# plugwatch.net
KiCad netlist of a schematic drawn in EAGLE
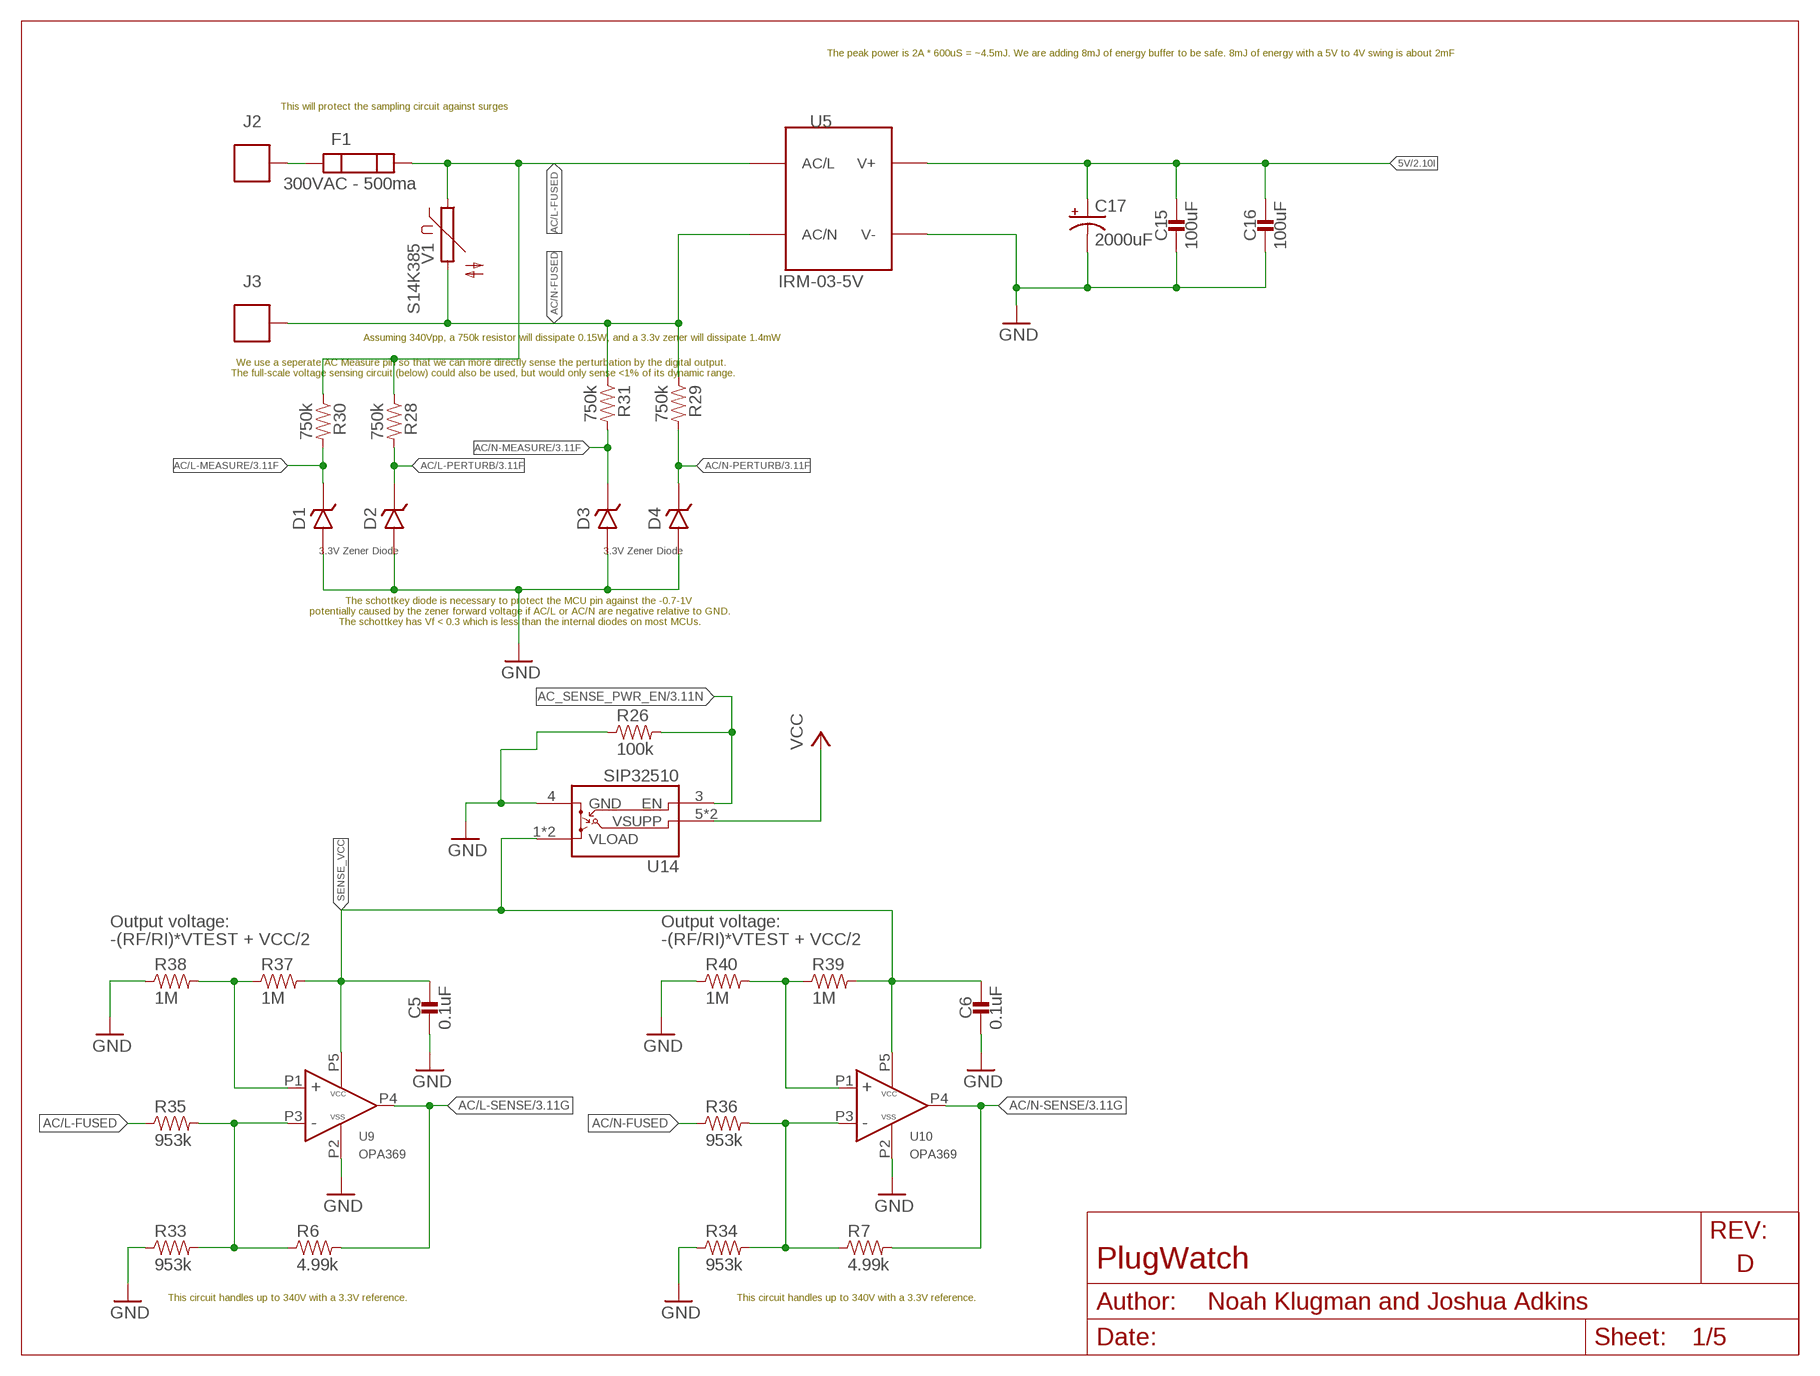
[diagram p0: schematic, sheet 1]
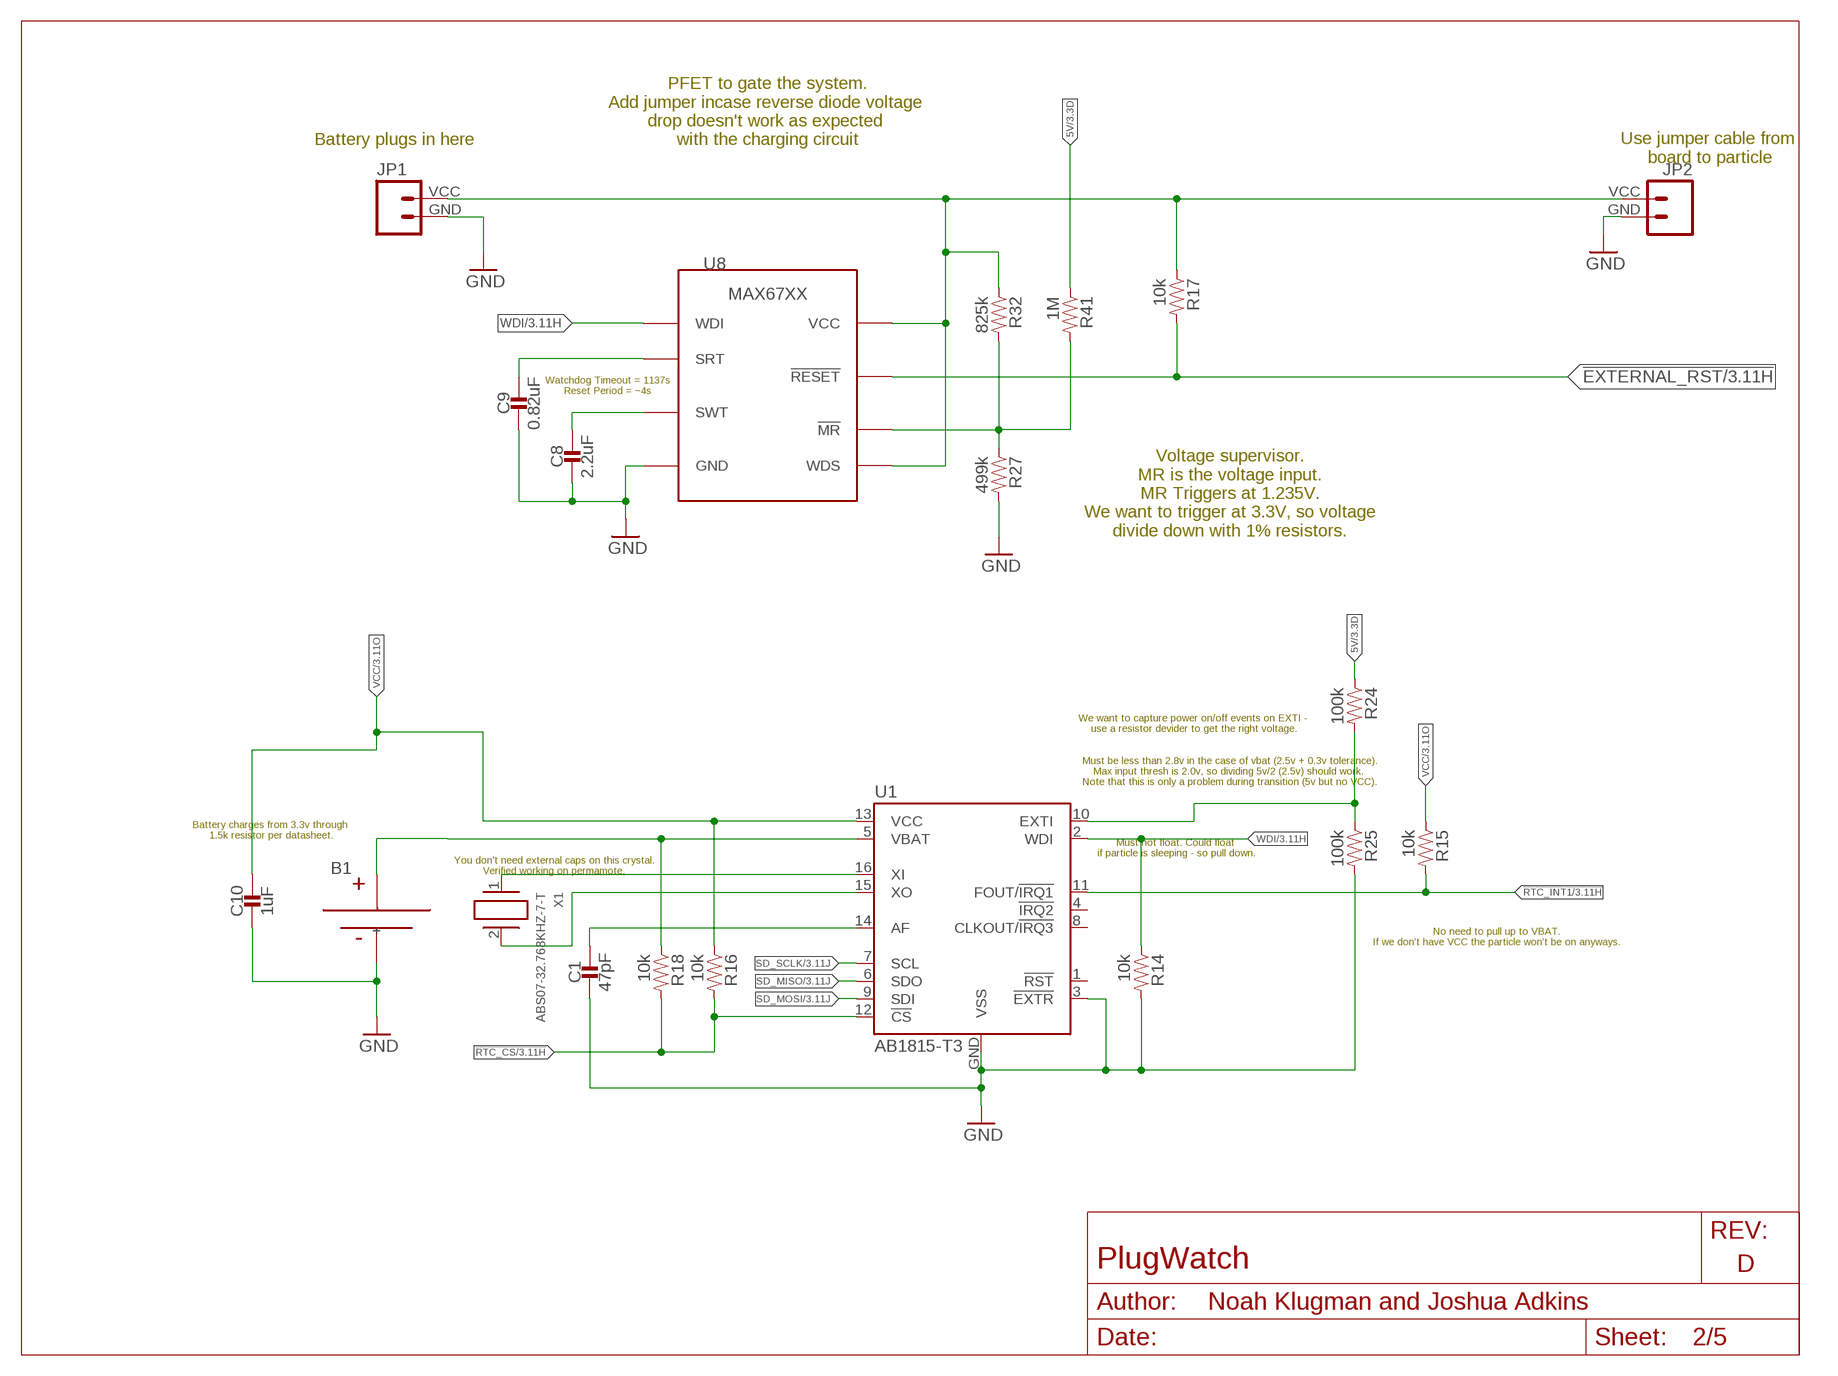
[diagram p1: schematic, sheet 2]
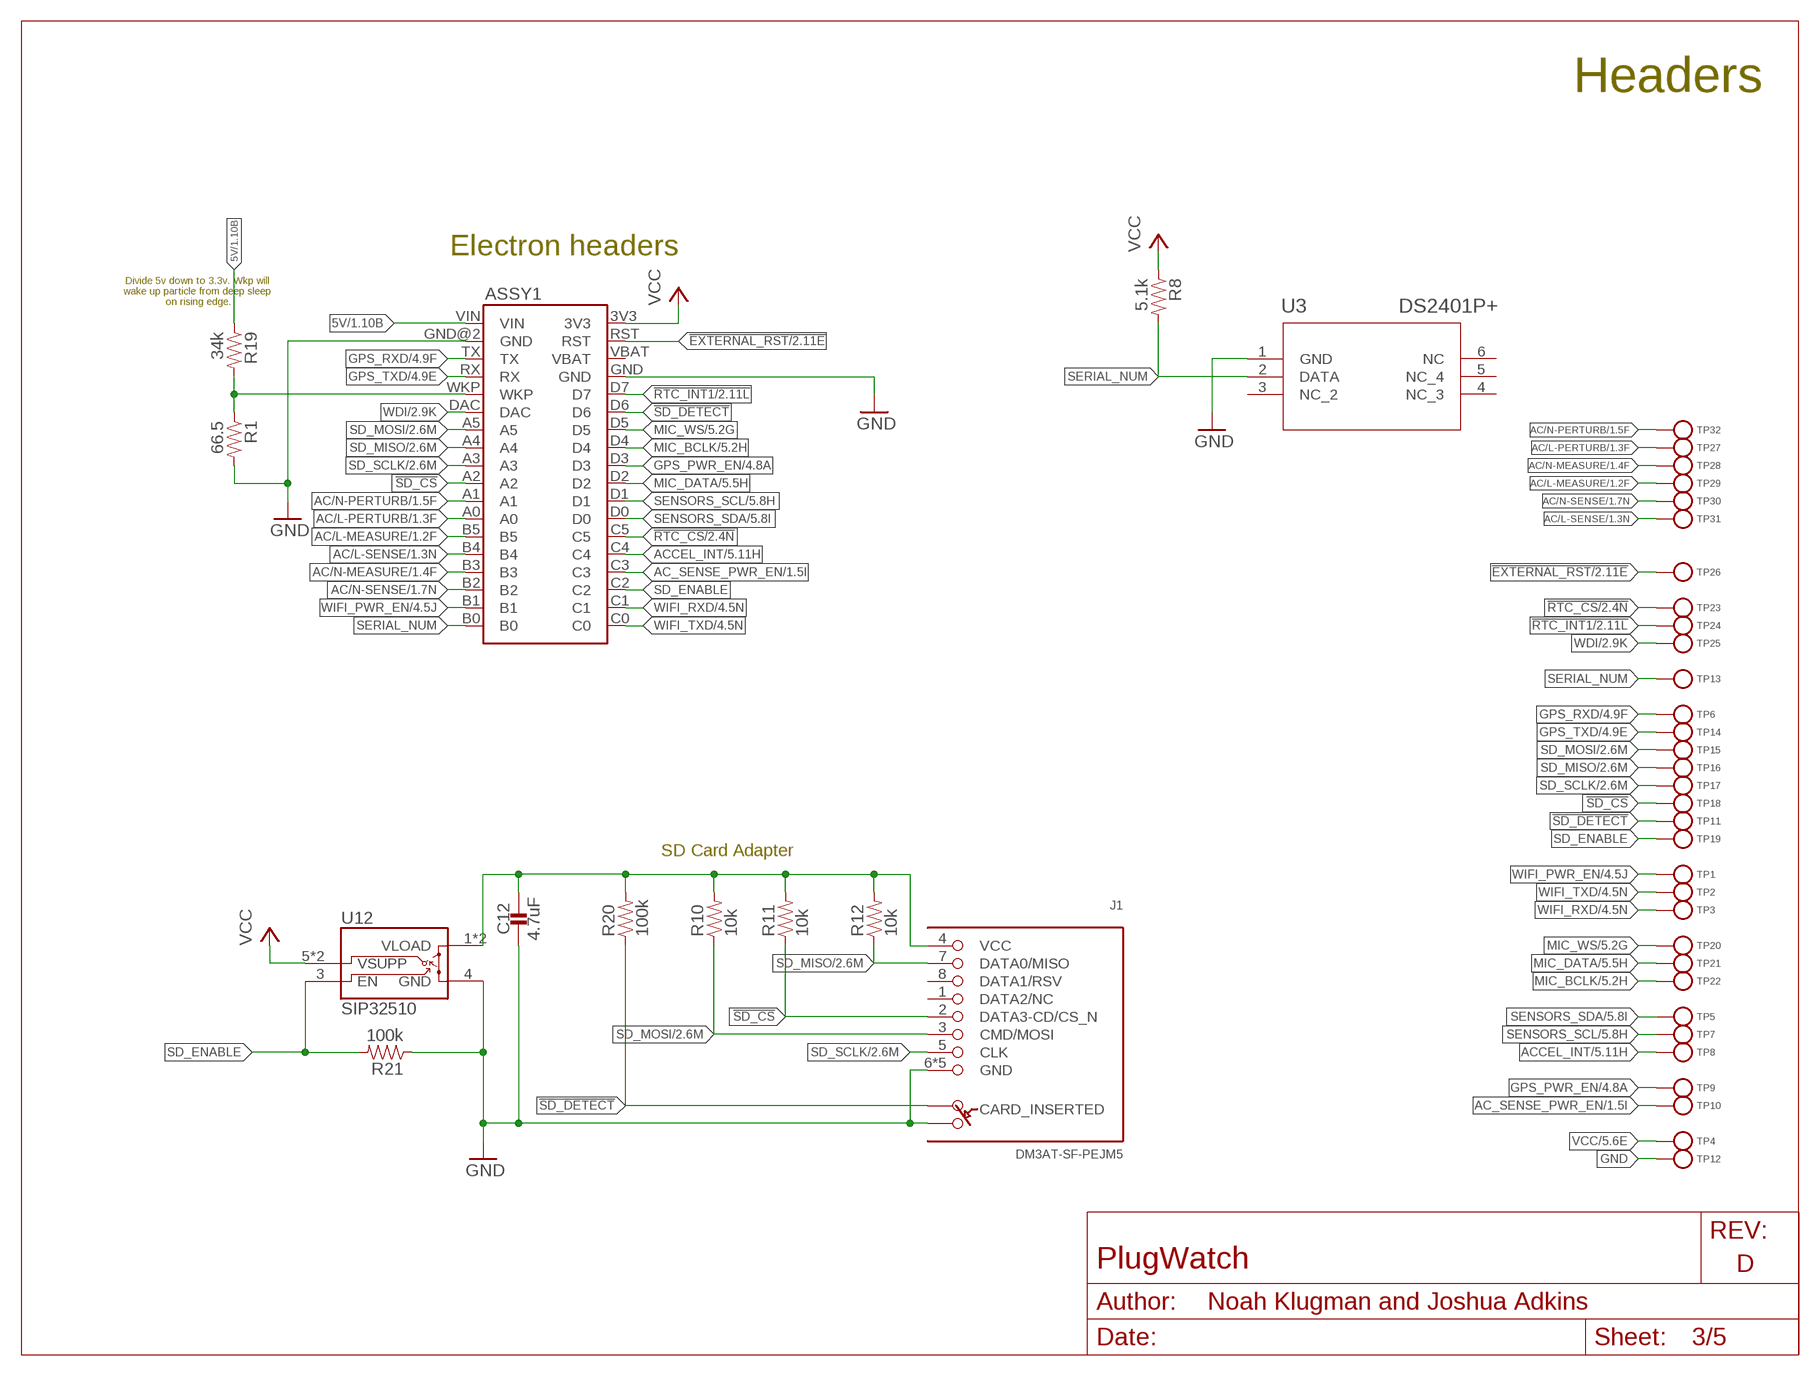
[diagram p2: schematic, sheet 3]
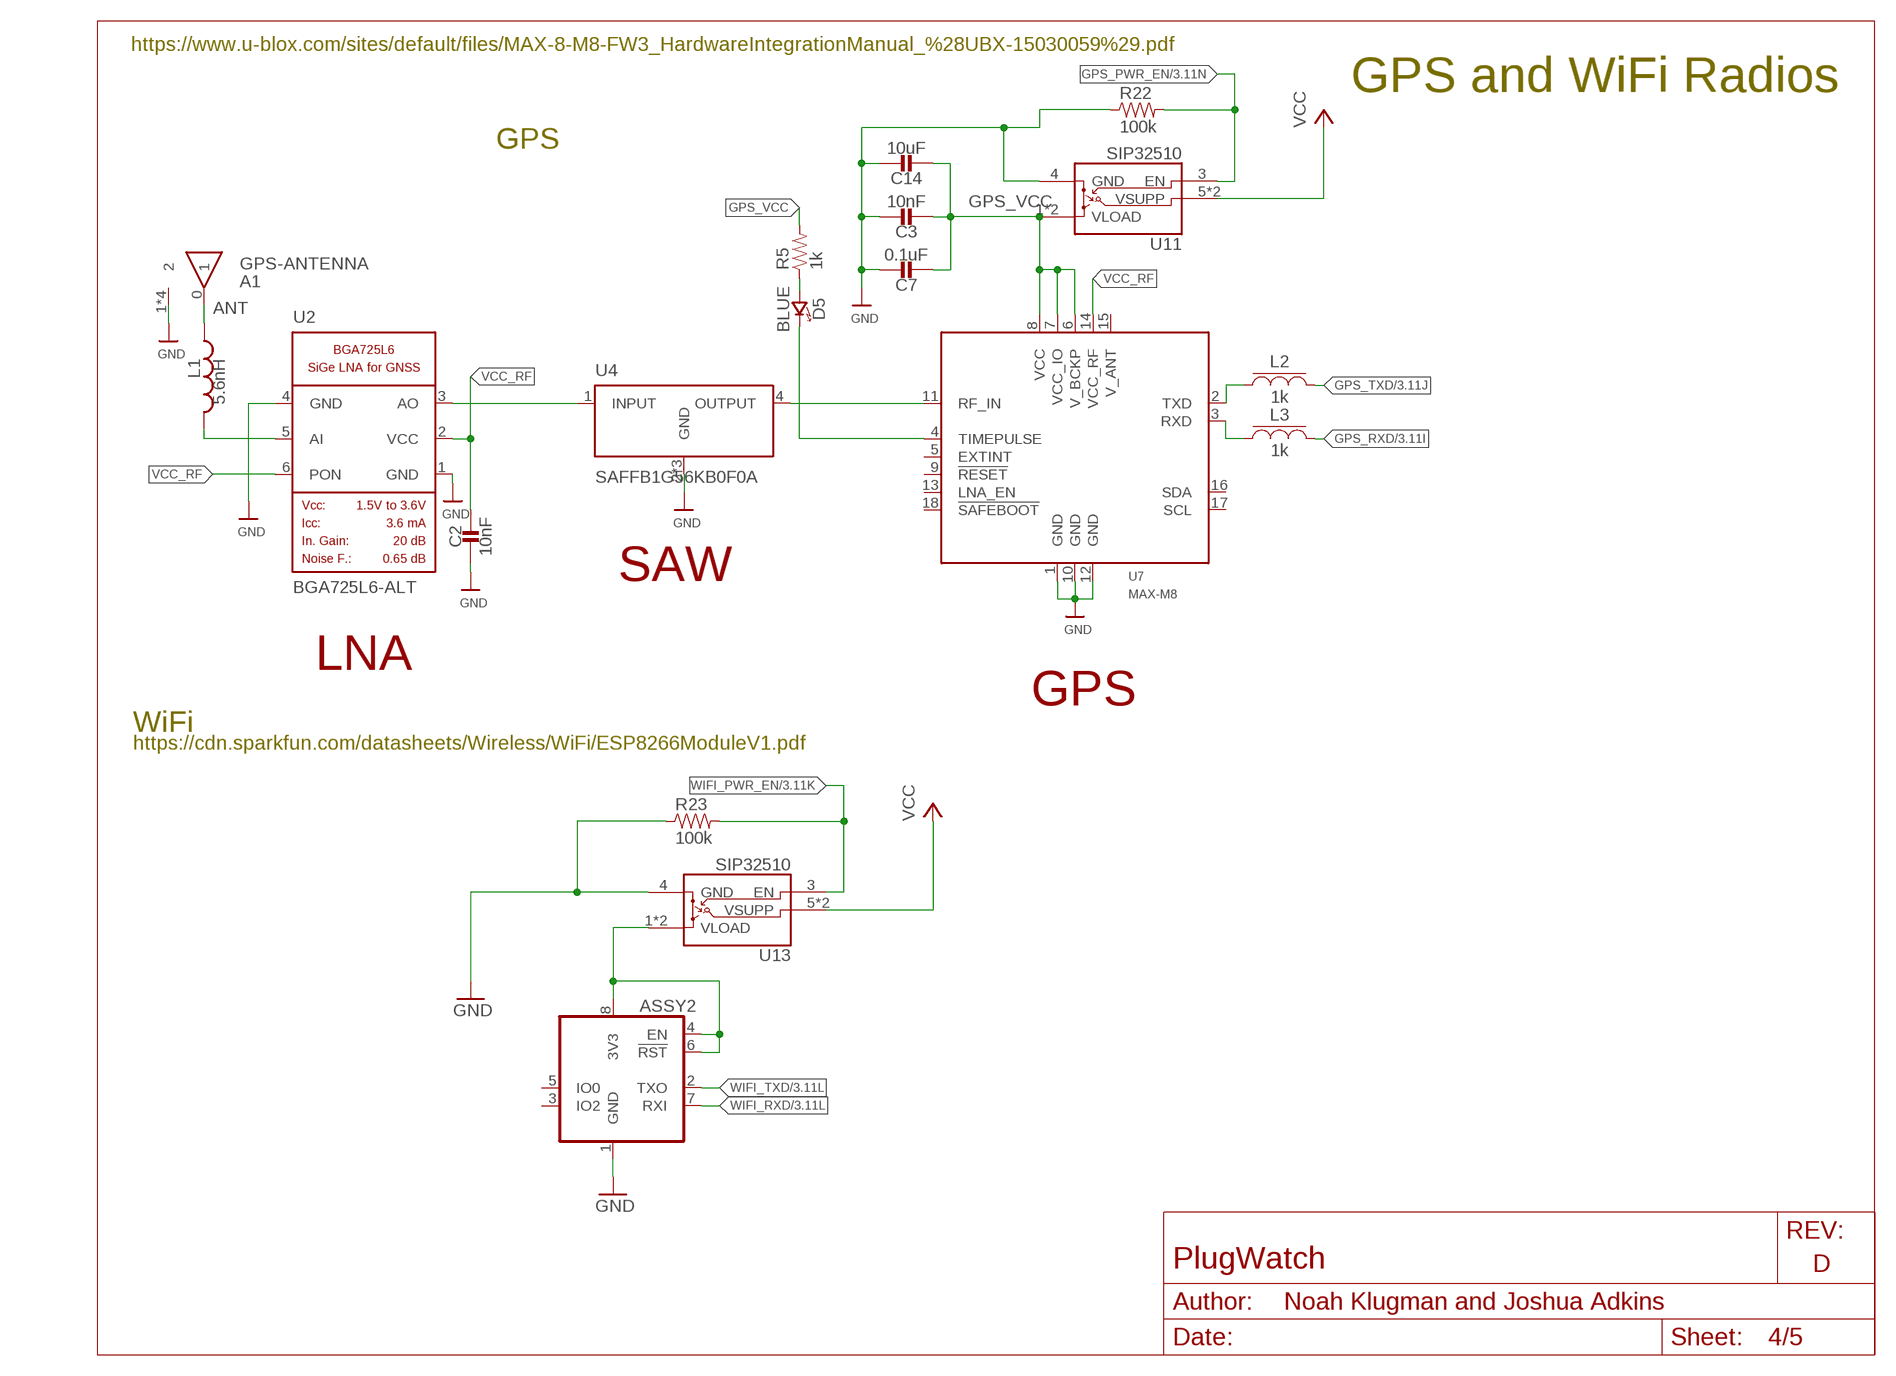
[diagram p3: schematic, sheet 4]
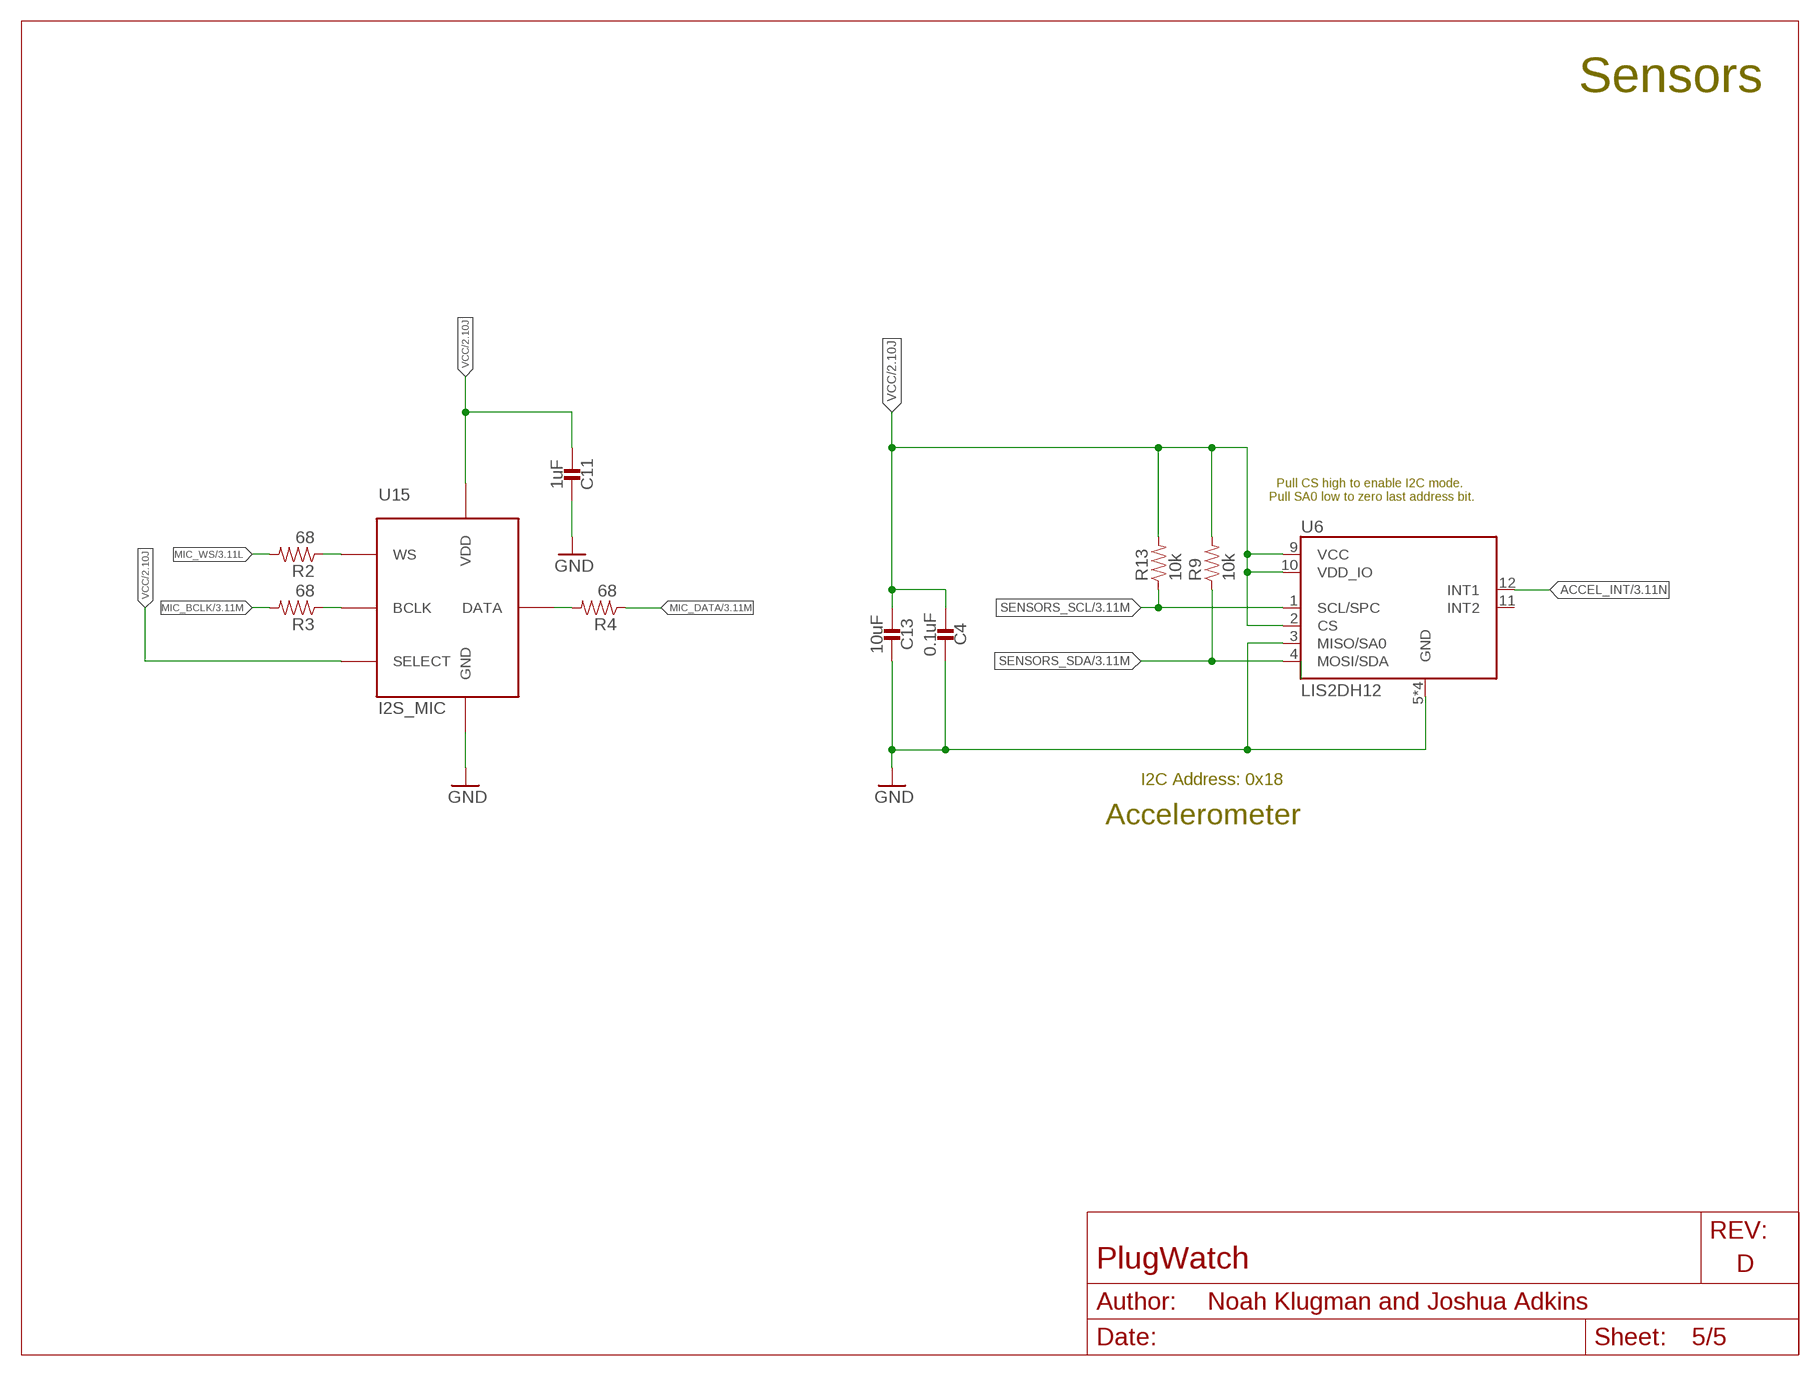
[diagram p4: schematic, sheet 5]

(export (version "E")
  (design (tool "Eeschema 10.0.6"))
  (components
    (comp (ref "A1")
      (value "GPS-ANTENNA")
      (footprint "eagle-import:ANT1818B00BT1516S")
      (description "PATCH ANT GPS/GLO CP SMD")
      (fields (field (name "MANUFACTURER") "Yageo") (field (name "MPN") "ANT1818B00BT1516S"))
      (libsource (lib "eagle-import") (part "GPS-ANTENNA"))
    )
    (comp (ref "ASSY2")
      (value "WRL-13678")
      (footprint "eagle-import:WRL-13678")
      (libsource (lib "eagle-import") (part "WRL-13678"))
    )
    (comp (ref "C2")
      (value "10nF")
      (footprint "eagle-import:0402_CAP")
      (description "CAP CER 10000PF 16V X7R 0402")
      (fields
        (field (name "MANUFACTURER") "Murata Electronics North America")
        (field (name "MPN") "GRM155R71C103KA01D")
      )
      (libsource (lib "eagle-import") (part "CAPACITOR0402_CAP"))
    )
    (comp (ref "C3")
      (value "10nF")
      (footprint "eagle-import:0402_CAP")
      (description "CAP CER 10000PF 16V X7R 0402")
      (fields
        (field (name "MANUFACTURER") "Murata Electronics North America")
        (field (name "MPN") "GRM155R71C103KA01D")
      )
      (libsource (lib "eagle-import") (part "CAPACITOR0402_CAP"))
    )
    (comp (ref "C7")
      (value "0.1uF")
      (footprint "eagle-import:0402_CAP")
      (description "CAP CER 0.1UF 10V X5R 0402")
      (fields (field (name "MANUFACTURER") "Yageo") (field (name "MPN") "CC0402KRX5R6BB104"))
      (libsource (lib "eagle-import") (part "CAPACITOR0402_CAP"))
    )
    (comp (ref "C14")
      (value "10uF")
      (footprint "eagle-import:0402_CAP")
      (description "CAP CER 10UF 6.3V X5R 0402")
      (fields
        (field (name "MANUFACTURER") "Murata Electronics North America")
        (field (name "MPN") "GRJ155R60J106ME11D")
      )
      (libsource (lib "eagle-import") (part "CAPACITOR0402_CAP"))
    )
    (comp (ref "D5")
      (value "BLUE")
      (footprint "eagle-import:LED-0603")
      (description "LED BLUE CLEAR SMD")
      (fields (field (name "MANUFACTURER") "Lite-On Inc.") (field (name "MPN") "LTST-C194TBKT"))
      (libsource (lib "eagle-import") (part "LED0603"))
    )
    (comp (ref "L1")
      (value "5.6nH")
      (footprint "eagle-import:0402_CAP")
      (description "FIXED IND 5.6NH 1.77A 40 MOHM")
      (fields (field (name "MANUFACTURER") "Murata") (field (name "MPN") "LQW15AN5N6B80D"))
      (libsource (lib "eagle-import") (part "INDUCTOR0402"))
    )
    (comp (ref "L2")
      (value "1k")
      (footprint "eagle-import:0402_CAP")
      (description "FERRITE BEAD 1 KOHM 0402 1LN")
      (fields (field (name "MANUFACTURER") "Murata") (field (name "MPN") "BLM15HD102SN1D"))
      (libsource (lib "eagle-import") (part "FERRITE_BEAD0402"))
    )
    (comp (ref "L3")
      (value "1k")
      (footprint "eagle-import:0402_CAP")
      (description "FERRITE BEAD 1 KOHM 0402 1LN")
      (fields (field (name "MANUFACTURER") "Murata") (field (name "MPN") "BLM15HD102SN1D"))
      (libsource (lib "eagle-import") (part "FERRITE_BEAD0402"))
    )
    (comp (ref "R5")
      (value "1k")
      (footprint "eagle-import:0402_RES")
      (description "RES SMD 1K OHM 1% 1/16W 0402")
      (fields (field (name "MANUFACTURER") "Stackpole Electronics") (field (name "MPN") "RMCF0402FT1K00"))
      (libsource (lib "eagle-import") (part "RESISTOR0402_RES"))
    )
    (comp (ref "R22")
      (value "100k")
      (footprint "eagle-import:0402_RES")
      (description "RES SMD 100K OHM 1% 1/16W 0402")
      (fields (field (name "MANUFACTURER") "Vishay Dale") (field (name "MPN") "CRCW0402100KFKED"))
      (libsource (lib "eagle-import") (part "RESISTOR0402_RES"))
    )
    (comp (ref "R23")
      (value "100k")
      (footprint "eagle-import:0402_RES")
      (description "RES SMD 100K OHM 1% 1/16W 0402")
      (fields (field (name "MANUFACTURER") "Vishay Dale") (field (name "MPN") "CRCW0402100KFKED"))
      (libsource (lib "eagle-import") (part "RESISTOR0402_RES"))
    )
    (comp (ref "U2")
      (value "BGA725L6-ALT")
      (footprint "eagle-import:LNA-TSLP-6-2-ALT")
      (description "IC AMP MMIC RF LNA 20DB TSLP-6")
      (fields (field (name "MANUFACTURER") "Infineon") (field (name "MPN") "BGA725L6E6327FTSA1"))
      (libsource (lib "eagle-import") (part "BGA725L6-ALT"))
    )
    (comp (ref "U4")
      (value "SAFFB1G56KB0F0A")
      (footprint "eagle-import:QCS5I")
      (description "FILTER SAW 1.582GHZ 5SMD")
      (fields (field (name "MANUFACTURER") "Taiyo Yuden") (field (name "MPN") "F6QA1G582H2JM-J"))
      (libsource (lib "eagle-import") (part "FILTERS"))
    )
    (comp (ref "U7")
      (value "MAX-M8")
      (footprint "eagle-import:MAX-M8")
      (description "IC RECEIVER GPS/GNSS 18LCC")
      (fields (field (name "MANUFACTURER") "u-blox") (field (name "MPN") "MAX-M8Q-0"))
      (libsource (lib "eagle-import") (part "MAX-M8"))
    )
    (comp (ref "U11")
      (value "SIP32510")
      (footprint "eagle-import:TSOT23-6")
      (fields (field (name "MANUFACTURER") "Vishay") (field (name "MPN") "SIP32510DT-T1-GE3"))
      (libsource (lib "eagle-import") (part "SIP32510"))
    )
    (comp (ref "U13")
      (value "SIP32510")
      (footprint "eagle-import:TSOT23-6")
      (fields (field (name "MANUFACTURER") "Vishay") (field (name "MPN") "SIP32510DT-T1-GE3"))
      (libsource (lib "eagle-import") (part "SIP32510"))
    )
    (comp (ref "B1")
      (value "MS518SE")
      (footprint "eagle-import:MS518SE-FL35E")
      (fields (field (name "MANUFACTURER") "Seiko") (field (name "MPN") "MS518SE-FL35E"))
      (libsource (lib "eagle-import") (part "MS518SE"))
    )
    (comp (ref "C1")
      (value "47pF")
      (footprint "eagle-import:0402_CAP")
      (description "CAP CER 47PF 100V C0G/NP0 0402")
      (fields
        (field (name "MANUFACTURER") "Murata Electronics North America")
        (field (name "MPN") "GRM1555C2A470JA01D")
      )
      (libsource (lib "eagle-import") (part "CAPACITOR0402_CAP"))
    )
    (comp (ref "C8")
      (value "2.2uF")
      (footprint "eagle-import:0402_CAP")
      (fields
        (field (name "MANUFACTURER") "Murata Electronics North America")
        (field (name "MPN") "GRM155C70J225KE11D")
      )
      (libsource (lib "eagle-import") (part "CAPACITOR0402_CAP"))
    )
    (comp (ref "C9")
      (value "0.82uF")
      (footprint "eagle-import:0402_CAP")
      (fields
        (field (name "MANUFACTURER") "Murata Electronics North America")
        (field (name "MPN") "GRM155C80J824KE15D")
      )
      (libsource (lib "eagle-import") (part "CAPACITOR0402_CAP"))
    )
    (comp (ref "C10")
      (value "1uF")
      (footprint "eagle-import:0402_CAP")
      (description "CAP CER 1UF 10V X7S 0402")
      (fields
        (field (name "MANUFACTURER") "Murata Electronics North America")
        (field (name "MPN") "GCM155C71A105KE38D")
      )
      (libsource (lib "eagle-import") (part "CAPACITOR0402_CAP"))
    )
    (comp (ref "JP1")
      (value "M024UCON-15767")
      (footprint "eagle-import:JST-2-SMD-VERT")
      (description "CONN HEADER PH TOP 2POS 2MM SMD")
      (fields
        (field (name "MANUFACTURER") "JST Sales America Inc.")
        (field (name "MPN") "B2B-PH-SM4-TB(LF)(SN)")
      )
      (libsource (lib "eagle-import") (part "M024UCON-15767"))
    )
    (comp (ref "JP2")
      (value "M024UCON-15767")
      (footprint "eagle-import:JST-2-SMD-VERT")
      (description "CONN HEADER PH TOP 2POS 2MM SMD")
      (fields
        (field (name "MANUFACTURER") "JST Sales America Inc.")
        (field (name "MPN") "B2B-PH-SM4-TB(LF)(SN)")
      )
      (libsource (lib "eagle-import") (part "M024UCON-15767"))
    )
    (comp (ref "R14")
      (value "10k")
      (footprint "eagle-import:0402_RES")
      (description "RES SMD 10K OHM 1% 1/16W 0402")
      (fields
        (field (name "MANUFACTURER") "Stackpole Electronics Inc. ")
        (field (name "MPN") "RMCF0402FT10K0 ")
      )
      (libsource (lib "eagle-import") (part "RESISTOR0402_RES"))
    )
    (comp (ref "R15")
      (value "10k")
      (footprint "eagle-import:0402_RES")
      (description "RES SMD 10K OHM 1% 1/16W 0402")
      (fields
        (field (name "MANUFACTURER") "Stackpole Electronics Inc. ")
        (field (name "MPN") "RMCF0402FT10K0 ")
      )
      (libsource (lib "eagle-import") (part "RESISTOR0402_RES"))
    )
    (comp (ref "R16")
      (value "10k")
      (footprint "eagle-import:0402_RES")
      (description "RES SMD 10K OHM 1% 1/16W 0402")
      (fields
        (field (name "MANUFACTURER") "Stackpole Electronics Inc. ")
        (field (name "MPN") "RMCF0402FT10K0 ")
      )
      (libsource (lib "eagle-import") (part "RESISTOR0402_RES"))
    )
    (comp (ref "R17")
      (value "10k")
      (footprint "eagle-import:0402_RES")
      (description "RES SMD 10K OHM 1% 1/16W 0402")
      (fields
        (field (name "MANUFACTURER") "Stackpole Electronics Inc. ")
        (field (name "MPN") "RMCF0402FT10K0 ")
      )
      (libsource (lib "eagle-import") (part "RESISTOR0402_RES"))
    )
    (comp (ref "R18")
      (value "10k")
      (footprint "eagle-import:0402_RES")
      (description "RES SMD 10K OHM 1% 1/16W 0402")
      (fields
        (field (name "MANUFACTURER") "Stackpole Electronics Inc. ")
        (field (name "MPN") "RMCF0402FT10K0 ")
      )
      (libsource (lib "eagle-import") (part "RESISTOR0402_RES"))
    )
    (comp (ref "R24")
      (value "100k")
      (footprint "eagle-import:0402_RES")
      (description "RES SMD 100K OHM 1% 1/16W 0402")
      (fields (field (name "MANUFACTURER") "Vishay Dale") (field (name "MPN") "CRCW0402100KFKED"))
      (libsource (lib "eagle-import") (part "RESISTOR0402_RES"))
    )
    (comp (ref "R25")
      (value "100k")
      (footprint "eagle-import:0402_RES")
      (description "RES SMD 100K OHM 1% 1/16W 0402")
      (fields (field (name "MANUFACTURER") "Vishay Dale") (field (name "MPN") "CRCW0402100KFKED"))
      (libsource (lib "eagle-import") (part "RESISTOR0402_RES"))
    )
    (comp (ref "R27")
      (value "499k")
      (footprint "eagle-import:0402_RES")
      (description "RES SMD 499K OHM 1% 1/10W 0402")
      (fields
        (field (name "MANUFACTURER") "Panasonic Electronic Components")
        (field (name "MPN") "ERJ-2RKF4993X")
      )
      (libsource (lib "eagle-import") (part "RESISTOR0402_RES"))
    )
    (comp (ref "R32")
      (value "825k")
      (footprint "eagle-import:0402_RES")
      (description "RES SMD 825K OHM 1% 1/10W 0402")
      (fields
        (field (name "MANUFACTURER") "Panasonic Electronic Components")
        (field (name "MPN") "ERJ-2RKF8253X")
      )
      (libsource (lib "eagle-import") (part "RESISTOR0402_RES"))
    )
    (comp (ref "R41")
      (value "1M")
      (footprint "eagle-import:0402_RES")
      (description "RES 1M OHM 1% 1/16W 0402")
      (fields
        (field (name "MANUFACTURER") "Stackpole Electronics Inc.")
        (field (name "MPN") "RMCF0402FT1M00")
      )
      (libsource (lib "eagle-import") (part "RESISTOR0402_RES"))
    )
    (comp (ref "U1")
      (value "AB1815-T3")
      (footprint "eagle-import:QFN-16-3MM")
      (fields (field (name "MANUFACTURER") "Abracon"))
      (libsource (lib "eagle-import") (part "AB1815-T3"))
    )
    (comp (ref "U8")
      (value "MAX67XXMAX6749MAX67XX")
      (footprint "eagle-import:SOT-23-8")
      (fields (field (name "MANUFACTURER") "Maxim Integrated") (field (name "MPN") "MAX6749KA+T"))
      (libsource (lib "eagle-import") (part "MAX67XXMAX67XXMAX6749"))
    )
    (comp (ref "X1")
      (value "ABS07-32.768KHZ-7-T")
      (footprint "eagle-import:2-SMD")
      (fields (field (name "MANUFACTURER") "ABRACON") (field (name "MPN") "ABS07-32.768KHZ-7-T "))
      (libsource (lib "eagle-import") (part "ABS07-32.768KHZ-7-T"))
    )
    (comp (ref "C4")
      (value "0.1uF")
      (footprint "eagle-import:0402_CAP")
      (description "CAP CER 0.1UF 10V X5R 0402")
      (fields (field (name "MANUFACTURER") "Yageo") (field (name "MPN") "CC0402KRX5R6BB104"))
      (libsource (lib "eagle-import") (part "CAPACITOR0402_CAP"))
    )
    (comp (ref "C11")
      (value "1uF")
      (footprint "eagle-import:0402_CAP")
      (description "CAP CER 1UF 10V X7S 0402")
      (fields
        (field (name "MANUFACTURER") "Murata Electronics North America")
        (field (name "MPN") "GCM155C71A105KE38D")
      )
      (libsource (lib "eagle-import") (part "CAPACITOR0402_CAP"))
    )
    (comp (ref "C13")
      (value "10uF")
      (footprint "eagle-import:0402_CAP")
      (description "CAP CER 10UF 6.3V X5R 0402")
      (fields
        (field (name "MANUFACTURER") "Murata Electronics North America")
        (field (name "MPN") "GRJ155R60J106ME11D")
      )
      (libsource (lib "eagle-import") (part "CAPACITOR0402_CAP"))
    )
    (comp (ref "R2")
      (value "68")
      (footprint "eagle-import:0402_RES")
      (description "RES SMD 68 OHM 1% 1/16W 0402")
      (fields (field (name "MANUFACTURER") "Yageo") (field (name "MPN") "RC0402FR-0768RL"))
      (libsource (lib "eagle-import") (part "RESISTOR0402_RES"))
    )
    (comp (ref "R3")
      (value "68")
      (footprint "eagle-import:0402_RES")
      (description "RES SMD 68 OHM 1% 1/16W 0402")
      (fields (field (name "MANUFACTURER") "Yageo") (field (name "MPN") "RC0402FR-0768RL"))
      (libsource (lib "eagle-import") (part "RESISTOR0402_RES"))
    )
    (comp (ref "R4")
      (value "68")
      (footprint "eagle-import:0402_RES")
      (description "RES SMD 68 OHM 1% 1/16W 0402")
      (fields (field (name "MANUFACTURER") "Yageo") (field (name "MPN") "RC0402FR-0768RL"))
      (libsource (lib "eagle-import") (part "RESISTOR0402_RES"))
    )
    (comp (ref "R9")
      (value "10k")
      (footprint "eagle-import:0402_RES")
      (description "RES SMD 10K OHM 1% 1/16W 0402")
      (fields
        (field (name "MANUFACTURER") "Stackpole Electronics Inc. ")
        (field (name "MPN") "RMCF0402FT10K0 ")
      )
      (libsource (lib "eagle-import") (part "RESISTOR0402_RES"))
    )
    (comp (ref "R13")
      (value "10k")
      (footprint "eagle-import:0402_RES")
      (description "RES SMD 10K OHM 1% 1/16W 0402")
      (fields
        (field (name "MANUFACTURER") "Stackpole Electronics Inc. ")
        (field (name "MPN") "RMCF0402FT10K0 ")
      )
      (libsource (lib "eagle-import") (part "RESISTOR0402_RES"))
    )
    (comp (ref "U6")
      (value "LIS2DH12")
      (footprint "eagle-import:LGA-12")
      (fields
        (field (name "MANUFACTURER") "STMicroelectronics")
        (field (name "MPN") "LIS2DW12TR")
        (field (name "DIGIKEY") "497-14851-1-ND")
        (field (name "MOUSER") "511-LIS2DH12TR")
        (field (name "MPN_1") "LIS2DH12TR")
      )
      (libsource (lib "eagle-import") (part "LIS2DW12"))
    )
    (comp (ref "U15")
      (value "SPH0645LM4H-B")
      (footprint "eagle-import:SPH0465")
      (fields (field (name "MANUFACTURER") "Knowles"))
      (libsource (lib "eagle-import") (part "SPH0645LM4H-B"))
    )
    (comp (ref "C5")
      (value "0.1uF")
      (footprint "eagle-import:0402_CAP")
      (description "CAP CER 0.1UF 10V X5R 0402")
      (fields (field (name "MANUFACTURER") "Yageo") (field (name "MPN") "CC0402KRX5R6BB104"))
      (libsource (lib "eagle-import") (part "CAPACITOR0402_CAP"))
    )
    (comp (ref "C6")
      (value "0.1uF")
      (footprint "eagle-import:0402_CAP")
      (description "CAP CER 0.1UF 10V X5R 0402")
      (fields (field (name "MANUFACTURER") "Yageo") (field (name "MPN") "CC0402KRX5R6BB104"))
      (libsource (lib "eagle-import") (part "CAPACITOR0402_CAP"))
    )
    (comp (ref "C15")
      (value "100uF")
      (footprint "eagle-import:1210_CAP")
      (description "CAP CER 100UF 6.3V X7S 1210")
      (fields
        (field (name "MANUFACTURER") "Murata Electronics North America")
        (field (name "MPN") "GRM32EC70J107ME15L")
      )
      (libsource (lib "eagle-import") (part "CAPACITOR1210_CAP"))
    )
    (comp (ref "C16")
      (value "100uF")
      (footprint "eagle-import:1210_CAP")
      (description "CAP CER 100UF 6.3V X7S 1210")
      (fields
        (field (name "MANUFACTURER") "Murata Electronics North America")
        (field (name "MPN") "GRM32EC70J107ME15L")
      )
      (libsource (lib "eagle-import") (part "CAPACITOR1210_CAP"))
    )
    (comp (ref "C17")
      (value "2000uF")
      (footprint "eagle-import:E5-13")
      (description "CAP ALUM 2000UF 20% 6.3V T/H")
      (fields
        (field (name "MANUFACTURER") "Panasonic Electronic Components")
        (field (name "MPN") "EEU-FS0J202B")
      )
      (libsource (lib "eagle-import") (part "CPOL-USE5-13"))
    )
    (comp (ref "D1")
      (value "DIODE_ZENERSOT323")
      (footprint "eagle-import:SOD323")
      (description "DIODE ZENER 3.3V 200MW SOD323F")
      (fields (field (name "MANUFACTURER") "ON Semiconductor ") (field (name "MPN") "MM3Z3V3B "))
      (libsource (lib "eagle-import") (part "DIODE_ZENERSOT323"))
    )
    (comp (ref "D2")
      (value "DIODE_ZENERSOT323")
      (footprint "eagle-import:SOD323")
      (description "DIODE ZENER 3.3V 200MW SOD323F")
      (fields (field (name "MANUFACTURER") "ON Semiconductor ") (field (name "MPN") "MM3Z3V3B "))
      (libsource (lib "eagle-import") (part "DIODE_ZENERSOT323"))
    )
    (comp (ref "D3")
      (value "DIODE_ZENERSOT323")
      (footprint "eagle-import:SOD323")
      (description "DIODE ZENER 3.3V 200MW SOD323F")
      (fields (field (name "MANUFACTURER") "ON Semiconductor ") (field (name "MPN") "MM3Z3V3B "))
      (libsource (lib "eagle-import") (part "DIODE_ZENERSOT323"))
    )
    (comp (ref "D4")
      (value "DIODE_ZENERSOT323")
      (footprint "eagle-import:SOD323")
      (description "DIODE ZENER 3.3V 200MW SOD323F")
      (fields (field (name "MANUFACTURER") "ON Semiconductor ") (field (name "MPN") "MM3Z3V3B "))
      (libsource (lib "eagle-import") (part "DIODE_ZENERSOT323"))
    )
    (comp (ref "F1")
      (value "300VAC - 500ma")
      (footprint "eagle-import:MIRCRO_FUSE_5MM")
      (description "FUSE BRD MNT 500MA 350VAC 100VDC")
      (fields (field (name "MANUFACTURER") "Bel Fuse Inc") (field (name "MPN") "0697H0500-01"))
      (libsource (lib "eagle-import") (part "MICRO_FUSE500MA_350VAC"))
    )
    (comp (ref "J2")
      (value "SCREW_TERMNIAL_1")
      (footprint "eagle-import:360272-TERMINAL-BLOCK")
      (fields (field (name "MANUFACTURER") "METZ CONNECT USA Inc.") (field (name "MPN") "360272"))
      (libsource (lib "eagle-import") (part "SCREW_TERMNIAL_1"))
    )
    (comp (ref "J3")
      (value "SCREW_TERMNIAL_1")
      (footprint "eagle-import:360272-TERMINAL-BLOCK")
      (fields (field (name "MANUFACTURER") "METZ CONNECT USA Inc.") (field (name "MPN") "360272"))
      (libsource (lib "eagle-import") (part "SCREW_TERMNIAL_1"))
    )
    (comp (ref "R6")
      (value "4.99k")
      (footprint "eagle-import:0402_RES")
      (description "RES SMD 4.99K OHM 1% 1/10W 0402")
      (fields
        (field (name "MANUFACTURER") "Panasonic Electronic Components")
        (field (name "MPN") "ERJ-2RKF4991X")
      )
      (libsource (lib "eagle-import") (part "RESISTOR0402_RES"))
    )
    (comp (ref "R7")
      (value "4.99k")
      (footprint "eagle-import:0402_RES")
      (description "RES SMD 4.99K OHM 1% 1/10W 0402")
      (fields
        (field (name "MANUFACTURER") "Panasonic Electronic Components")
        (field (name "MPN") "ERJ-2RKF4991X")
      )
      (libsource (lib "eagle-import") (part "RESISTOR0402_RES"))
    )
    (comp (ref "R26")
      (value "100k")
      (footprint "eagle-import:0402_RES")
      (description "RES SMD 100K OHM 1% 1/16W 0402")
      (fields (field (name "MANUFACTURER") "Vishay Dale") (field (name "MPN") "CRCW0402100KFKED"))
      (libsource (lib "eagle-import") (part "RESISTOR0402_RES"))
    )
    (comp (ref "R28")
      (value "750k")
      (footprint "eagle-import:1206_RES_HIGH_CLEARANCE")
      (description "RES SMD 750K OHM 1% 1/4W 1206")
      (fields (field (name "MANUFACTURER") "Yageo") (field (name "MPN") "RC1206FR-07750KL"))
      (libsource (lib "eagle-import") (part "RESISTOR1206_RES_HIGH_CLEARANCE"))
    )
    (comp (ref "R29")
      (value "750k")
      (footprint "eagle-import:1206_RES_HIGH_CLEARANCE")
      (description "RES SMD 750K OHM 1% 1/4W 1206")
      (fields (field (name "MANUFACTURER") "Yageo") (field (name "MPN") "RC1206FR-07750KL"))
      (libsource (lib "eagle-import") (part "RESISTOR1206_RES_HIGH_CLEARANCE"))
    )
    (comp (ref "R30")
      (value "750k")
      (footprint "eagle-import:1206_RES_HIGH_CLEARANCE")
      (description "RES SMD 750K OHM 1% 1/4W 1206")
      (fields (field (name "MANUFACTURER") "Yageo") (field (name "MPN") "RC1206FR-07750KL"))
      (libsource (lib "eagle-import") (part "RESISTOR1206_RES_HIGH_CLEARANCE"))
    )
    (comp (ref "R31")
      (value "750k")
      (footprint "eagle-import:1206_RES_HIGH_CLEARANCE")
      (description "RES SMD 750K OHM 1% 1/4W 1206")
      (fields (field (name "MANUFACTURER") "Yageo") (field (name "MPN") "RC1206FR-07750KL"))
      (libsource (lib "eagle-import") (part "RESISTOR1206_RES_HIGH_CLEARANCE"))
    )
    (comp (ref "R33")
      (value "953k")
      (footprint "eagle-import:0402_RES")
      (description "RES SMD 953K OHM 1% 1/16W 0402")
      (fields (field (name "MANUFACTURER") "Yageo") (field (name "MPN") "RC0402FR-07953KL"))
      (libsource (lib "eagle-import") (part "RESISTOR0402_RES"))
    )
    (comp (ref "R34")
      (value "953k")
      (footprint "eagle-import:0402_RES")
      (description "RES SMD 953K OHM 1% 1/16W 0402")
      (fields (field (name "MANUFACTURER") "Yageo") (field (name "MPN") "RC0402FR-07953KL"))
      (libsource (lib "eagle-import") (part "RESISTOR0402_RES"))
    )
    (comp (ref "R35")
      (value "953k")
      (footprint "eagle-import:1206_RES_HIGH_CLEARANCE")
      (fields
        (field (name "MANUFACTURER") "Panasonic Electronic Components")
        (field (name "MPN") "ERA-8AEB9533V")
      )
      (libsource (lib "eagle-import") (part "RESISTOR1206_RES_HIGH_CLEARANCE"))
    )
    (comp (ref "R36")
      (value "953k")
      (footprint "eagle-import:1206_RES_HIGH_CLEARANCE")
      (fields
        (field (name "MANUFACTURER") "Panasonic Electronic Components")
        (field (name "MPN") "ERA-8AEB9533V")
      )
      (libsource (lib "eagle-import") (part "RESISTOR1206_RES_HIGH_CLEARANCE"))
    )
    (comp (ref "R37")
      (value "1M")
      (footprint "eagle-import:0402_RES")
      (description "RES 1M OHM 1% 1/16W 0402")
      (fields
        (field (name "MANUFACTURER") "Stackpole Electronics Inc.")
        (field (name "MPN") "RMCF0402FT1M00")
      )
      (libsource (lib "eagle-import") (part "RESISTOR0402_RES"))
    )
    (comp (ref "R38")
      (value "1M")
      (footprint "eagle-import:0402_RES")
      (description "RES 1M OHM 1% 1/16W 0402")
      (fields
        (field (name "MANUFACTURER") "Stackpole Electronics Inc.")
        (field (name "MPN") "RMCF0402FT1M00")
      )
      (libsource (lib "eagle-import") (part "RESISTOR0402_RES"))
    )
    (comp (ref "R39")
      (value "1M")
      (footprint "eagle-import:0402_RES")
      (description "RES 1M OHM 1% 1/16W 0402")
      (fields
        (field (name "MANUFACTURER") "Stackpole Electronics Inc.")
        (field (name "MPN") "RMCF0402FT1M00")
      )
      (libsource (lib "eagle-import") (part "RESISTOR0402_RES"))
    )
    (comp (ref "R40")
      (value "1M")
      (footprint "eagle-import:0402_RES")
      (description "RES 1M OHM 1% 1/16W 0402")
      (fields
        (field (name "MANUFACTURER") "Stackpole Electronics Inc.")
        (field (name "MPN") "RMCF0402FT1M00")
      )
      (libsource (lib "eagle-import") (part "RESISTOR0402_RES"))
    )
    (comp (ref "U5")
      (value "IRM-03-5V")
      (footprint "eagle-import:IRM-03")
      (fields (field (name "MANUFACTURER") "Mean Well USA") (field (name "MPN") "IRM-03-5"))
      (libsource (lib "eagle-import") (part "IRM-03-5V"))
    )
    (comp (ref "U9")
      (value "OPA369")
      (footprint "eagle-import:SC70-5")
      (fields
        (field (name "MANUFACTURER") "Texas Instruments")
        (field (name "MPN") "OPA369AIDCKR")
        (field (name "DIGIKEY") "296-25252-1-ND")
      )
      (libsource (lib "eagle-import") (part "OPA369"))
    )
    (comp (ref "U10")
      (value "OPA369")
      (footprint "eagle-import:SC70-5")
      (fields
        (field (name "MANUFACTURER") "Texas Instruments")
        (field (name "MPN") "OPA369AIDCKR")
        (field (name "DIGIKEY") "296-25252-1-ND")
      )
      (libsource (lib "eagle-import") (part "OPA369"))
    )
    (comp (ref "U14")
      (value "SIP32510")
      (footprint "eagle-import:TSOT23-6")
      (fields (field (name "MANUFACTURER") "Vishay") (field (name "MPN") "SIP32510DT-T1-GE3"))
      (libsource (lib "eagle-import") (part "SIP32510"))
    )
    (comp (ref "V1")
      (value "S14K385")
      (footprint "eagle-import:S14K385")
      (description "VARISTOR 620V 5KA DISC 14MM")
      (fields (field (name "MANUFACTURER") "EPCOS (TDK)") (field (name "MPN") "B72214S2381K101"))
      (libsource (lib "eagle-import") (part "S14K385"))
    )
    (comp (ref "ASSY1")
      (value "ELECTRON")
      (footprint "eagle-import:ELECTRON_SINGLE-ROW")
      (description "18 Position header")
      (fields (field (name "MANUFACTURER") "Sullins") (field (name "MPN") "PPPC181LFBN-RC"))
      (libsource (lib "eagle-import") (part "ELECTRON"))
    )
    (comp (ref "C12")
      (value "4.7uF")
      (footprint "eagle-import:0402_CAP")
      (description "CAP CER 4.7UF 6.3V X5R 0402")
      (fields (field (name "MANUFACTURER") "TDK") (field (name "MPN") "C1005X5R0J475K050BC"))
      (libsource (lib "eagle-import") (part "CAPACITOR0402_CAP"))
    )
    (comp (ref "J1")
      (value "DM3AT-SF-PEJM5")
      (footprint "eagle-import:DM3AT-SF-PEJM5")
      (fields (field (name "MANUFACTURER") "Hirose Electric Co Ltd"))
      (libsource (lib "eagle-import") (part "DM3AT-SF-PEJM5"))
    )
    (comp (ref "R1")
      (value "66.5")
      (footprint "eagle-import:0402_RES")
      (description "RES SMD 66.5 OHM 1% 1/16W 0402")
      (fields (field (name "MANUFACTURER") "Yageo") (field (name "MPN") "RC0402FR-0766R5L"))
      (libsource (lib "eagle-import") (part "RESISTOR0402_RES"))
    )
    (comp (ref "R8")
      (value "5.1k")
      (footprint "eagle-import:0402_RES")
      (description "RES SMD 5.1K OHM 1% 1/10W 0402")
      (fields
        (field (name "MANUFACTURER") "Panasonic Electronic Components")
        (field (name "MPN") "ERJ-2RKF5101X")
      )
      (libsource (lib "eagle-import") (part "RESISTOR0402_RES"))
    )
    (comp (ref "R10")
      (value "10k")
      (footprint "eagle-import:0402_RES")
      (description "RES SMD 10K OHM 1% 1/16W 0402")
      (fields
        (field (name "MANUFACTURER") "Stackpole Electronics Inc. ")
        (field (name "MPN") "RMCF0402FT10K0 ")
      )
      (libsource (lib "eagle-import") (part "RESISTOR0402_RES"))
    )
    (comp (ref "R11")
      (value "10k")
      (footprint "eagle-import:0402_RES")
      (description "RES SMD 10K OHM 1% 1/16W 0402")
      (fields
        (field (name "MANUFACTURER") "Stackpole Electronics Inc. ")
        (field (name "MPN") "RMCF0402FT10K0 ")
      )
      (libsource (lib "eagle-import") (part "RESISTOR0402_RES"))
    )
    (comp (ref "R12")
      (value "10k")
      (footprint "eagle-import:0402_RES")
      (description "RES SMD 10K OHM 1% 1/16W 0402")
      (fields
        (field (name "MANUFACTURER") "Stackpole Electronics Inc. ")
        (field (name "MPN") "RMCF0402FT10K0 ")
      )
      (libsource (lib "eagle-import") (part "RESISTOR0402_RES"))
    )
    (comp (ref "R19")
      (value "34k")
      (footprint "eagle-import:0402_RES")
      (description "RES SMD 34K OHM 1% 1/10W 0402")
      (fields
        (field (name "MANUFACTURER") "Panasonic Electronic Components")
        (field (name "MPN") "ERJ-2RKF3402X")
      )
      (libsource (lib "eagle-import") (part "RESISTOR0402_RES"))
    )
    (comp (ref "R20")
      (value "100k")
      (footprint "eagle-import:0402_RES")
      (description "RES SMD 100K OHM 1% 1/16W 0402")
      (fields (field (name "MANUFACTURER") "Vishay Dale") (field (name "MPN") "CRCW0402100KFKED"))
      (libsource (lib "eagle-import") (part "RESISTOR0402_RES"))
    )
    (comp (ref "R21")
      (value "100k")
      (footprint "eagle-import:0402_RES")
      (description "RES SMD 100K OHM 1% 1/16W 0402")
      (fields (field (name "MANUFACTURER") "Vishay Dale") (field (name "MPN") "CRCW0402100KFKED"))
      (libsource (lib "eagle-import") (part "RESISTOR0402_RES"))
    )
    (comp (ref "TP1")
      (value "TEST_POINT_0.040IN")
      (footprint "eagle-import:TESTPOINT_0.040IN")
      (libsource (lib "eagle-import") (part "TEST_POINT_0.040IN"))
    )
    (comp (ref "TP2")
      (value "TEST_POINT_0.040IN")
      (footprint "eagle-import:TESTPOINT_0.040IN")
      (libsource (lib "eagle-import") (part "TEST_POINT_0.040IN"))
    )
    (comp (ref "TP3")
      (value "TEST_POINT_0.040IN")
      (footprint "eagle-import:TESTPOINT_0.040IN")
      (libsource (lib "eagle-import") (part "TEST_POINT_0.040IN"))
    )
    (comp (ref "TP4")
      (value "TEST_POINT_0.040IN")
      (footprint "eagle-import:TESTPOINT_0.040IN")
      (libsource (lib "eagle-import") (part "TEST_POINT_0.040IN"))
    )
    (comp (ref "TP5")
      (value "TEST_POINT_0.040IN")
      (footprint "eagle-import:TESTPOINT_0.040IN")
      (libsource (lib "eagle-import") (part "TEST_POINT_0.040IN"))
    )
    (comp (ref "TP6")
      (value "TEST_POINT_0.040IN")
      (footprint "eagle-import:TESTPOINT_0.040IN")
      (libsource (lib "eagle-import") (part "TEST_POINT_0.040IN"))
    )
    (comp (ref "TP7")
      (value "TEST_POINT_0.040IN")
      (footprint "eagle-import:TESTPOINT_0.040IN")
      (libsource (lib "eagle-import") (part "TEST_POINT_0.040IN"))
    )
    (comp (ref "TP8")
      (value "TEST_POINT_0.040IN")
      (footprint "eagle-import:TESTPOINT_0.040IN")
      (libsource (lib "eagle-import") (part "TEST_POINT_0.040IN"))
    )
    (comp (ref "TP9")
      (value "TEST_POINT_0.040IN")
      (footprint "eagle-import:TESTPOINT_0.040IN")
      (libsource (lib "eagle-import") (part "TEST_POINT_0.040IN"))
    )
    (comp (ref "TP10")
      (value "TEST_POINT_0.040IN")
      (footprint "eagle-import:TESTPOINT_0.040IN")
      (libsource (lib "eagle-import") (part "TEST_POINT_0.040IN"))
    )
    (comp (ref "TP11")
      (value "TEST_POINT_0.040IN")
      (footprint "eagle-import:TESTPOINT_0.040IN")
      (libsource (lib "eagle-import") (part "TEST_POINT_0.040IN"))
    )
    (comp (ref "TP12")
      (value "TEST_POINT_0.040IN")
      (footprint "eagle-import:TESTPOINT_0.040IN")
      (libsource (lib "eagle-import") (part "TEST_POINT_0.040IN"))
    )
    (comp (ref "TP13")
      (value "TEST_POINT_0.040IN")
      (footprint "eagle-import:TESTPOINT_0.040IN")
      (libsource (lib "eagle-import") (part "TEST_POINT_0.040IN"))
    )
    (comp (ref "TP14")
      (value "TEST_POINT_0.040IN")
      (footprint "eagle-import:TESTPOINT_0.040IN")
      (libsource (lib "eagle-import") (part "TEST_POINT_0.040IN"))
    )
    (comp (ref "TP15")
      (value "TEST_POINT_0.040IN")
      (footprint "eagle-import:TESTPOINT_0.040IN")
      (libsource (lib "eagle-import") (part "TEST_POINT_0.040IN"))
    )
    (comp (ref "TP16")
      (value "TEST_POINT_0.040IN")
      (footprint "eagle-import:TESTPOINT_0.040IN")
      (libsource (lib "eagle-import") (part "TEST_POINT_0.040IN"))
    )
    (comp (ref "TP17")
      (value "TEST_POINT_0.040IN")
      (footprint "eagle-import:TESTPOINT_0.040IN")
      (libsource (lib "eagle-import") (part "TEST_POINT_0.040IN"))
    )
    (comp (ref "TP18")
      (value "TEST_POINT_0.040IN")
      (footprint "eagle-import:TESTPOINT_0.040IN")
      (libsource (lib "eagle-import") (part "TEST_POINT_0.040IN"))
    )
    (comp (ref "TP19")
      (value "TEST_POINT_0.040IN")
      (footprint "eagle-import:TESTPOINT_0.040IN")
      (libsource (lib "eagle-import") (part "TEST_POINT_0.040IN"))
    )
    (comp (ref "TP20")
      (value "TEST_POINT_0.040IN")
      (footprint "eagle-import:TESTPOINT_0.040IN")
      (libsource (lib "eagle-import") (part "TEST_POINT_0.040IN"))
    )
    (comp (ref "TP21")
      (value "TEST_POINT_0.040IN")
      (footprint "eagle-import:TESTPOINT_0.040IN")
      (libsource (lib "eagle-import") (part "TEST_POINT_0.040IN"))
    )
    (comp (ref "TP22")
      (value "TEST_POINT_0.040IN")
      (footprint "eagle-import:TESTPOINT_0.040IN")
      (libsource (lib "eagle-import") (part "TEST_POINT_0.040IN"))
    )
    (comp (ref "TP23")
      (value "TEST_POINT_0.040IN")
      (footprint "eagle-import:TESTPOINT_0.040IN")
      (libsource (lib "eagle-import") (part "TEST_POINT_0.040IN"))
    )
    (comp (ref "TP24")
      (value "TEST_POINT_0.040IN")
      (footprint "eagle-import:TESTPOINT_0.040IN")
      (libsource (lib "eagle-import") (part "TEST_POINT_0.040IN"))
    )
    (comp (ref "TP25")
      (value "TEST_POINT_0.040IN")
      (footprint "eagle-import:TESTPOINT_0.040IN")
      (libsource (lib "eagle-import") (part "TEST_POINT_0.040IN"))
    )
    (comp (ref "TP26")
      (value "TEST_POINT_0.040IN")
      (footprint "eagle-import:TESTPOINT_0.040IN")
      (libsource (lib "eagle-import") (part "TEST_POINT_0.040IN"))
    )
    (comp (ref "TP27")
      (value "TEST_POINT_0.040IN")
      (footprint "eagle-import:TESTPOINT_0.040IN")
      (libsource (lib "eagle-import") (part "TEST_POINT_0.040IN"))
    )
    (comp (ref "TP28")
      (value "TEST_POINT_0.040IN")
      (footprint "eagle-import:TESTPOINT_0.040IN")
      (libsource (lib "eagle-import") (part "TEST_POINT_0.040IN"))
    )
    (comp (ref "TP29")
      (value "TEST_POINT_0.040IN")
      (footprint "eagle-import:TESTPOINT_0.040IN")
      (libsource (lib "eagle-import") (part "TEST_POINT_0.040IN"))
    )
    (comp (ref "TP30")
      (value "TEST_POINT_0.040IN")
      (footprint "eagle-import:TESTPOINT_0.040IN")
      (libsource (lib "eagle-import") (part "TEST_POINT_0.040IN"))
    )
    (comp (ref "TP31")
      (value "TEST_POINT_0.040IN")
      (footprint "eagle-import:TESTPOINT_0.040IN")
      (libsource (lib "eagle-import") (part "TEST_POINT_0.040IN"))
    )
    (comp (ref "TP32")
      (value "TEST_POINT_0.040IN")
      (footprint "eagle-import:TESTPOINT_0.040IN")
      (libsource (lib "eagle-import") (part "TEST_POINT_0.040IN"))
    )
    (comp (ref "U3")
      (value "DS2401P+")
      (footprint "eagle-import:21-0382")
      (fields (field (name "MANUFACTURER") "Maxim Integrated") (field (name "SPICEPREFIX") "X"))
      (libsource (lib "eagle-import") (part "DS2401P+"))
    )
    (comp (ref "U12")
      (value "SIP32510")
      (footprint "eagle-import:TSOT23-6")
      (fields (field (name "MANUFACTURER") "Vishay") (field (name "MPN") "SIP32510DT-T1-GE3"))
      (libsource (lib "eagle-import") (part "SIP32510"))
    )
  )
  (nets
    (net (code "1") (name "5V") (class "Default")
      (node (ref "ASSY1") (pin "VIN") (pinfunction "VIN_VIN") (pintype "power_in"))
      (node (ref "C15") (pin "1") (pinfunction "1_1") (pintype "bidirectional"))
      (node (ref "C16") (pin "1") (pinfunction "1_1") (pintype "bidirectional"))
      (node (ref "C17") (pin "+") (pinfunction "+_+") (pintype "passive"))
      (node (ref "R19") (pin "1") (pinfunction "1_1") (pintype "passive"))
      (node (ref "R24") (pin "1") (pinfunction "1_1") (pintype "passive"))
      (node (ref "R41") (pin "1") (pinfunction "1_1") (pintype "passive"))
      (node (ref "U5") (pin "V+") (pinfunction "V+_V+") (pintype "bidirectional"))
    )
    (net (code "2") (name "ACCEL_INT") (class "Default")
      (node (ref "ASSY1") (pin "C4") (pinfunction "C4_C4") (pintype "bidirectional"))
      (node (ref "TP8") (pin "TESTPOINT") (pinfunction "TESTPOINT_TESTPOINT") (pintype "bidirectional"))
      (node (ref "U6") (pin "12") (pinfunction "INT1_12") (pintype "bidirectional"))
    )
    (net (code "3") (name "AC_SENSE_PWR_EN") (class "Default")
      (node (ref "ASSY1") (pin "C3") (pinfunction "C3_C3") (pintype "bidirectional"))
      (node (ref "R26") (pin "2") (pinfunction "2_2") (pintype "passive"))
      (node (ref "TP10") (pin "TESTPOINT") (pinfunction "TESTPOINT_TESTPOINT") (pintype "bidirectional"))
      (node (ref "U14") (pin "3") (pinfunction "EN_3") (pintype "bidirectional"))
    )
    (net (code "4") (name "AC{slash}L-FUSED") (class "Default")
      (node (ref "F1") (pin "P$2") (pinfunction "P$2_P$2") (pintype "bidirectional"))
      (node (ref "R28") (pin "1") (pinfunction "1_1") (pintype "passive"))
      (node (ref "R30") (pin "1") (pinfunction "1_1") (pintype "passive"))
      (node (ref "R35") (pin "1") (pinfunction "1_1") (pintype "passive"))
      (node (ref "U5") (pin "AC/L") (pinfunction "AC/L_AC/L") (pintype "bidirectional"))
      (node (ref "V1") (pin "1") (pinfunction "1_1") (pintype "passive"))
    )
    (net (code "5") (name "AC{slash}L-MEASURE") (class "Default")
      (node (ref "ASSY1") (pin "B5") (pinfunction "B5_B5") (pintype "bidirectional"))
      (node (ref "D1") (pin "P$1") (pinfunction "CATHODE_P$1") (pintype "bidirectional"))
      (node (ref "R30") (pin "2") (pinfunction "2_2") (pintype "passive"))
      (node (ref "TP29") (pin "TESTPOINT") (pinfunction "TESTPOINT_TESTPOINT") (pintype "bidirectional"))
    )
    (net (code "6") (name "AC{slash}L-PERTURB") (class "Default")
      (node (ref "ASSY1") (pin "A0") (pinfunction "A0_A0") (pintype "bidirectional"))
      (node (ref "D2") (pin "P$1") (pinfunction "CATHODE_P$1") (pintype "bidirectional"))
      (node (ref "R28") (pin "2") (pinfunction "2_2") (pintype "passive"))
      (node (ref "TP27") (pin "TESTPOINT") (pinfunction "TESTPOINT_TESTPOINT") (pintype "bidirectional"))
    )
    (net (code "7") (name "AC{slash}L-SENSE") (class "Default")
      (node (ref "ASSY1") (pin "B4") (pinfunction "B4_B4") (pintype "bidirectional"))
      (node (ref "R6") (pin "2") (pinfunction "2_2") (pintype "passive"))
      (node (ref "TP31") (pin "TESTPOINT") (pinfunction "TESTPOINT_TESTPOINT") (pintype "bidirectional"))
      (node (ref "U9") (pin "P4") (pinfunction "OUT_P4") (pintype "bidirectional"))
    )
    (net (code "8") (name "AC{slash}N-FUSED") (class "Default")
      (node (ref "J3") (pin "P$1") (pinfunction "P$1_P$1") (pintype "bidirectional"))
      (node (ref "J3") (pin "P$2") (pinfunction "P$1_P$2") (pintype "bidirectional"))
      (node (ref "R29") (pin "1") (pinfunction "1_1") (pintype "passive"))
      (node (ref "R31") (pin "1") (pinfunction "1_1") (pintype "passive"))
      (node (ref "R36") (pin "1") (pinfunction "1_1") (pintype "passive"))
      (node (ref "U5") (pin "AC/N") (pinfunction "AC/N_AC/N") (pintype "bidirectional"))
      (node (ref "V1") (pin "2") (pinfunction "2_2") (pintype "passive"))
    )
    (net (code "9") (name "AC{slash}N-MEASURE") (class "Default")
      (node (ref "ASSY1") (pin "B3") (pinfunction "B3_B3") (pintype "bidirectional"))
      (node (ref "D3") (pin "P$1") (pinfunction "CATHODE_P$1") (pintype "bidirectional"))
      (node (ref "R31") (pin "2") (pinfunction "2_2") (pintype "passive"))
      (node (ref "TP28") (pin "TESTPOINT") (pinfunction "TESTPOINT_TESTPOINT") (pintype "bidirectional"))
    )
    (net (code "10") (name "AC{slash}N-PERTURB") (class "Default")
      (node (ref "ASSY1") (pin "A1") (pinfunction "A1_A1") (pintype "bidirectional"))
      (node (ref "D4") (pin "P$1") (pinfunction "CATHODE_P$1") (pintype "bidirectional"))
      (node (ref "R29") (pin "2") (pinfunction "2_2") (pintype "passive"))
      (node (ref "TP32") (pin "TESTPOINT") (pinfunction "TESTPOINT_TESTPOINT") (pintype "bidirectional"))
    )
    (net (code "11") (name "AC{slash}N-SENSE") (class "Default")
      (node (ref "ASSY1") (pin "B2") (pinfunction "B2_B2") (pintype "bidirectional"))
      (node (ref "R7") (pin "2") (pinfunction "2_2") (pintype "passive"))
      (node (ref "TP30") (pin "TESTPOINT") (pinfunction "TESTPOINT_TESTPOINT") (pintype "bidirectional"))
      (node (ref "U10") (pin "P4") (pinfunction "OUT_P4") (pintype "bidirectional"))
    )
    (net (code "12") (name "ANT") (class "Default")
      (node (ref "A1") (pin "0") (pinfunction "1_0") (pintype "output"))
      (node (ref "L1") (pin "2") (pinfunction "2_2") (pintype "bidirectional"))
    )
    (net (code "13") (name "GND") (class "Default")
      (node (ref "A1") (pin "1") (pinfunction "2_1") (pintype "power_in"))
      (node (ref "A1") (pin "2") (pinfunction "2_2") (pintype "power_in"))
      (node (ref "A1") (pin "3") (pinfunction "2_3") (pintype "power_in"))
      (node (ref "A1") (pin "4") (pinfunction "2_4") (pintype "power_in"))
      (node (ref "ASSY1") (pin "GND") (pinfunction "GND_GND") (pintype "power_in"))
      (node (ref "ASSY1") (pin "GND@2") (pinfunction "GND_GND@2") (pintype "power_in"))
      (node (ref "ASSY2") (pin "1") (pinfunction "GND_1") (pintype "power_in"))
      (node (ref "B1") (pin "-") (pinfunction "-_-") (pintype "bidirectional"))
      (node (ref "C1") (pin "2") (pinfunction "2_2") (pintype "bidirectional"))
      (node (ref "C10") (pin "2") (pinfunction "2_2") (pintype "bidirectional"))
      (node (ref "C11") (pin "2") (pinfunction "2_2") (pintype "bidirectional"))
      (node (ref "C12") (pin "2") (pinfunction "2_2") (pintype "bidirectional"))
      (node (ref "C13") (pin "2") (pinfunction "2_2") (pintype "bidirectional"))
      (node (ref "C14") (pin "1") (pinfunction "1_1") (pintype "bidirectional"))
      (node (ref "C15") (pin "2") (pinfunction "2_2") (pintype "bidirectional"))
      (node (ref "C16") (pin "2") (pinfunction "2_2") (pintype "bidirectional"))
      (node (ref "C17") (pin "-") (pinfunction "-_-") (pintype "passive"))
      (node (ref "C2") (pin "1") (pinfunction "1_1") (pintype "bidirectional"))
      (node (ref "C3") (pin "1") (pinfunction "1_1") (pintype "bidirectional"))
      (node (ref "C4") (pin "2") (pinfunction "2_2") (pintype "bidirectional"))
      (node (ref "C5") (pin "2") (pinfunction "2_2") (pintype "bidirectional"))
      (node (ref "C6") (pin "2") (pinfunction "2_2") (pintype "bidirectional"))
      (node (ref "C7") (pin "1") (pinfunction "1_1") (pintype "bidirectional"))
      (node (ref "C8") (pin "2") (pinfunction "2_2") (pintype "bidirectional"))
      (node (ref "C9") (pin "2") (pinfunction "2_2") (pintype "bidirectional"))
      (node (ref "D1") (pin "P$2") (pinfunction "ANODE_P$2") (pintype "bidirectional"))
      (node (ref "D2") (pin "P$2") (pinfunction "ANODE_P$2") (pintype "bidirectional"))
      (node (ref "D3") (pin "P$2") (pinfunction "ANODE_P$2") (pintype "bidirectional"))
      (node (ref "D4") (pin "P$2") (pinfunction "ANODE_P$2") (pintype "bidirectional"))
      (node (ref "J1") (pin "6") (pinfunction "GND_6") (pintype "bidirectional"))
      (node (ref "J1") (pin "B") (pinfunction "B_B") (pintype "bidirectional"))
      (node (ref "J1") (pin "MOUNT0") (pinfunction "GND_MOUNT0") (pintype "bidirectional"))
      (node (ref "J1") (pin "MOUNT1") (pinfunction "GND_MOUNT1") (pintype "bidirectional"))
      (node (ref "J1") (pin "MOUNT2") (pinfunction "GND_MOUNT2") (pintype "bidirectional"))
      (node (ref "J1") (pin "MOUNT3") (pinfunction "GND_MOUNT3") (pintype "bidirectional"))
      (node (ref "JP1") (pin "GND") (pinfunction "1_GND") (pintype "passive"))
      (node (ref "JP2") (pin "GND") (pinfunction "1_GND") (pintype "passive"))
      (node (ref "R1") (pin "2") (pinfunction "2_2") (pintype "passive"))
      (node (ref "R14") (pin "2") (pinfunction "2_2") (pintype "passive"))
      (node (ref "R21") (pin "1") (pinfunction "1_1") (pintype "passive"))
      (node (ref "R22") (pin "1") (pinfunction "1_1") (pintype "passive"))
      (node (ref "R23") (pin "1") (pinfunction "1_1") (pintype "passive"))
      (node (ref "R25") (pin "2") (pinfunction "2_2") (pintype "passive"))
      (node (ref "R26") (pin "1") (pinfunction "1_1") (pintype "passive"))
      (node (ref "R27") (pin "2") (pinfunction "2_2") (pintype "passive"))
      (node (ref "R33") (pin "1") (pinfunction "1_1") (pintype "passive"))
      (node (ref "R34") (pin "1") (pinfunction "1_1") (pintype "passive"))
      (node (ref "R38") (pin "1") (pinfunction "1_1") (pintype "passive"))
      (node (ref "R40") (pin "1") (pinfunction "1_1") (pintype "passive"))
      (node (ref "TP12") (pin "TESTPOINT") (pinfunction "TESTPOINT_TESTPOINT") (pintype "bidirectional"))
      (node (ref "U1") (pin "3") (pinfunction "~{EXTR}_3") (pintype "bidirectional"))
      (node (ref "U1") (pin "GND") (pinfunction "VSS_GND") (pintype "bidirectional"))
      (node (ref "U10") (pin "P2") (pinfunction "VSS_P2") (pintype "bidirectional"))
      (node (ref "U11") (pin "4") (pinfunction "GND_4") (pintype "bidirectional"))
      (node (ref "U12") (pin "4") (pinfunction "GND_4") (pintype "bidirectional"))
      (node (ref "U13") (pin "4") (pinfunction "GND_4") (pintype "bidirectional"))
      (node (ref "U14") (pin "4") (pinfunction "GND_4") (pintype "bidirectional"))
      (node (ref "U15") (pin "3") (pinfunction "GND_3") (pintype "bidirectional"))
      (node (ref "U2") (pin "1") (pinfunction "GND_1") (pintype "power_in"))
      (node (ref "U2") (pin "4") (pinfunction "GND_4") (pintype "power_in"))
      (node (ref "U3") (pin "1") (pinfunction "GND_1") (pintype "power_in"))
      (node (ref "U4") (pin "2") (pinfunction "GND_2") (pintype "power_in"))
      (node (ref "U4") (pin "3") (pinfunction "GND_3") (pintype "power_in"))
      (node (ref "U4") (pin "5") (pinfunction "GND_5") (pintype "power_in"))
      (node (ref "U5") (pin "V-") (pinfunction "V-_V-") (pintype "bidirectional"))
      (node (ref "U6") (pin "3") (pinfunction "MISO/SA0_3") (pintype "bidirectional"))
      (node (ref "U6") (pin "5") (pinfunction "GND_5") (pintype "bidirectional"))
      (node (ref "U6") (pin "6") (pinfunction "GND_6") (pintype "bidirectional"))
      (node (ref "U6") (pin "7") (pinfunction "GND_7") (pintype "bidirectional"))
      (node (ref "U6") (pin "8") (pinfunction "GND_8") (pintype "bidirectional"))
      (node (ref "U7") (pin "1") (pinfunction "GND_1") (pintype "bidirectional"))
      (node (ref "U7") (pin "10") (pinfunction "GND_10") (pintype "bidirectional"))
      (node (ref "U7") (pin "12") (pinfunction "GND_12") (pintype "bidirectional"))
      (node (ref "U8") (pin "4") (pinfunction "GND_4") (pintype "bidirectional"))
      (node (ref "U9") (pin "P2") (pinfunction "VSS_P2") (pintype "bidirectional"))
    )
    (net (code "14") (name "GPS_PWR_EN") (class "Default")
      (node (ref "ASSY1") (pin "D3") (pinfunction "D3_D3") (pintype "bidirectional"))
      (node (ref "R22") (pin "2") (pinfunction "2_2") (pintype "passive"))
      (node (ref "TP9") (pin "TESTPOINT") (pinfunction "TESTPOINT_TESTPOINT") (pintype "bidirectional"))
      (node (ref "U11") (pin "3") (pinfunction "EN_3") (pintype "bidirectional"))
    )
    (net (code "15") (name "GPS_RXD") (class "Default")
      (node (ref "ASSY1") (pin "TX") (pinfunction "TX_TX") (pintype "bidirectional"))
      (node (ref "L3") (pin "2") (pinfunction "P$2_2") (pintype "bidirectional"))
      (node (ref "TP6") (pin "TESTPOINT") (pinfunction "TESTPOINT_TESTPOINT") (pintype "bidirectional"))
    )
    (net (code "16") (name "GPS_TXD") (class "Default")
      (node (ref "ASSY1") (pin "RX") (pinfunction "RX_RX") (pintype "bidirectional"))
      (node (ref "L2") (pin "2") (pinfunction "P$2_2") (pintype "bidirectional"))
      (node (ref "TP14") (pin "TESTPOINT") (pinfunction "TESTPOINT_TESTPOINT") (pintype "bidirectional"))
    )
    (net (code "17") (name "GPS_VCC") (class "Default")
      (node (ref "C14") (pin "2") (pinfunction "2_2") (pintype "bidirectional"))
      (node (ref "C3") (pin "2") (pinfunction "2_2") (pintype "bidirectional"))
      (node (ref "C7") (pin "2") (pinfunction "2_2") (pintype "bidirectional"))
      (node (ref "R5") (pin "2") (pinfunction "2_2") (pintype "passive"))
      (node (ref "U11") (pin "1") (pinfunction "VLOAD_1") (pintype "bidirectional"))
      (node (ref "U11") (pin "2") (pinfunction "VLOAD_2") (pintype "bidirectional"))
      (node (ref "U7") (pin "6") (pinfunction "V_BCKP_6") (pintype "bidirectional"))
      (node (ref "U7") (pin "7") (pinfunction "VCC_IO_7") (pintype "bidirectional"))
      (node (ref "U7") (pin "8") (pinfunction "VCC_8") (pintype "bidirectional"))
    )
    (net (code "18") (name "MIC_BCLK") (class "Default")
      (node (ref "ASSY1") (pin "D4") (pinfunction "D4_D4") (pintype "bidirectional"))
      (node (ref "R3") (pin "2") (pinfunction "2_2") (pintype "passive"))
      (node (ref "TP22") (pin "TESTPOINT") (pinfunction "TESTPOINT_TESTPOINT") (pintype "bidirectional"))
    )
    (net (code "19") (name "MIC_DATA") (class "Default")
      (node (ref "ASSY1") (pin "D2") (pinfunction "D2_D2") (pintype "bidirectional"))
      (node (ref "R4") (pin "1") (pinfunction "1_1") (pintype "passive"))
      (node (ref "TP21") (pin "TESTPOINT") (pinfunction "TESTPOINT_TESTPOINT") (pintype "bidirectional"))
    )
    (net (code "20") (name "MIC_WS") (class "Default")
      (node (ref "ASSY1") (pin "D5") (pinfunction "D5_D5") (pintype "bidirectional"))
      (node (ref "R2") (pin "2") (pinfunction "2_2") (pintype "passive"))
      (node (ref "TP20") (pin "TESTPOINT") (pinfunction "TESTPOINT_TESTPOINT") (pintype "bidirectional"))
    )
    (net (code "21") (name "Net-(ASSY1-PadWKP)") (class "Default")
      (node (ref "ASSY1") (pin "WKP") (pinfunction "WKP_WKP") (pintype "bidirectional"))
      (node (ref "R1") (pin "1") (pinfunction "1_1") (pintype "passive"))
      (node (ref "R19") (pin "2") (pinfunction "2_2") (pintype "passive"))
    )
    (net (code "22") (name "Net-(ASSY2-3V3)") (class "Default")
      (node (ref "ASSY2") (pin "4") (pinfunction "EN_4") (pintype "bidirectional"))
      (node (ref "ASSY2") (pin "6") (pinfunction "~{RST}_6") (pintype "bidirectional"))
      (node (ref "ASSY2") (pin "8") (pinfunction "3V3_8") (pintype "power_in"))
      (node (ref "U13") (pin "1") (pinfunction "VLOAD_1") (pintype "bidirectional"))
      (node (ref "U13") (pin "2") (pinfunction "VLOAD_2") (pintype "bidirectional"))
    )
    (net (code "23") (name "Net-(D5-ANODE)") (class "Default")
      (node (ref "D5") (pin "A") (pinfunction "ANODE_A") (pintype "bidirectional"))
      (node (ref "R5") (pin "1") (pinfunction "1_1") (pintype "passive"))
    )
    (net (code "24") (name "Net-(D5-CATHODE)") (class "Default")
      (node (ref "D5") (pin "C") (pinfunction "CATHODE_C") (pintype "bidirectional"))
      (node (ref "U7") (pin "4") (pinfunction "TIMEPULSE_4") (pintype "bidirectional"))
    )
    (net (code "25") (name "Net-(F1-PadP$1)") (class "Default")
      (node (ref "F1") (pin "P$1") (pinfunction "P$1_P$1") (pintype "bidirectional"))
      (node (ref "J2") (pin "P$1") (pinfunction "P$1_P$1") (pintype "bidirectional"))
      (node (ref "J2") (pin "P$2") (pinfunction "P$1_P$2") (pintype "bidirectional"))
    )
    (net (code "26") (name "Net-(J1-VCC)") (class "Default")
      (node (ref "C12") (pin "1") (pinfunction "1_1") (pintype "bidirectional"))
      (node (ref "J1") (pin "4") (pinfunction "VCC_4") (pintype "bidirectional"))
      (node (ref "R10") (pin "2") (pinfunction "2_2") (pintype "passive"))
      (node (ref "R11") (pin "2") (pinfunction "2_2") (pintype "passive"))
      (node (ref "R12") (pin "2") (pinfunction "2_2") (pintype "passive"))
      (node (ref "R20") (pin "2") (pinfunction "2_2") (pintype "passive"))
      (node (ref "U12") (pin "1") (pinfunction "VLOAD_1") (pintype "bidirectional"))
      (node (ref "U12") (pin "2") (pinfunction "VLOAD_2") (pintype "bidirectional"))
    )
    (net (code "27") (name "Net-(JP1-2)") (class "Default")
      (node (ref "JP1") (pin "VCC") (pinfunction "2_VCC") (pintype "passive"))
      (node (ref "JP2") (pin "VCC") (pinfunction "2_VCC") (pintype "passive"))
      (node (ref "R17") (pin "1") (pinfunction "1_1") (pintype "passive"))
      (node (ref "R32") (pin "1") (pinfunction "1_1") (pintype "passive"))
      (node (ref "U8") (pin "5") (pinfunction "WDS_5") (pintype "bidirectional"))
      (node (ref "U8") (pin "8") (pinfunction "VCC_8") (pintype "bidirectional"))
    )
    (net (code "28") (name "Net-(L2-P$1)") (class "Default")
      (node (ref "L2") (pin "1") (pinfunction "P$1_1") (pintype "bidirectional"))
      (node (ref "U7") (pin "2") (pinfunction "TXD_2") (pintype "bidirectional"))
    )
    (net (code "29") (name "Net-(L3-P$1)") (class "Default")
      (node (ref "L3") (pin "1") (pinfunction "P$1_1") (pintype "bidirectional"))
      (node (ref "U7") (pin "3") (pinfunction "RXD_3") (pintype "bidirectional"))
    )
    (net (code "30") (name "Net-(U1-AF)") (class "Default")
      (node (ref "C1") (pin "1") (pinfunction "1_1") (pintype "bidirectional"))
      (node (ref "U1") (pin "14") (pinfunction "AF_14") (pintype "bidirectional"))
    )
    (net (code "31") (name "Net-(U1-EXTI)") (class "Default")
      (node (ref "R24") (pin "2") (pinfunction "2_2") (pintype "passive"))
      (node (ref "R25") (pin "1") (pinfunction "1_1") (pintype "passive"))
      (node (ref "U1") (pin "10") (pinfunction "EXTI_10") (pintype "bidirectional"))
    )
    (net (code "32") (name "Net-(U1-VBAT)") (class "Default")
      (node (ref "B1") (pin "+") (pinfunction "+_+") (pintype "bidirectional"))
      (node (ref "R18") (pin "1") (pinfunction "1_1") (pintype "passive"))
      (node (ref "U1") (pin "5") (pinfunction "VBAT_5") (pintype "bidirectional"))
    )
    (net (code "33") (name "Net-(U1-XI)") (class "Default")
      (node (ref "U1") (pin "16") (pinfunction "XI_16") (pintype "bidirectional"))
      (node (ref "X1") (pin "1") (pinfunction "1_1") (pintype "bidirectional"))
    )
    (net (code "34") (name "Net-(U1-XO)") (class "Default")
      (node (ref "U1") (pin "15") (pinfunction "XO_15") (pintype "bidirectional"))
      (node (ref "X1") (pin "2") (pinfunction "2_2") (pintype "bidirectional"))
    )
    (net (code "35") (name "Net-(U2-AI)") (class "Default")
      (node (ref "L1") (pin "1") (pinfunction "1_1") (pintype "bidirectional"))
      (node (ref "U2") (pin "5") (pinfunction "AI_5") (pintype "input"))
    )
    (net (code "36") (name "Net-(U2-AO)") (class "Default")
      (node (ref "U2") (pin "3") (pinfunction "AO_3") (pintype "output"))
      (node (ref "U4") (pin "1") (pinfunction "INPUT_1") (pintype "input"))
    )
    (net (code "37") (name "Net-(U4-OUTPUT)") (class "Default")
      (node (ref "U4") (pin "4") (pinfunction "OUTPUT_4") (pintype "bidirectional"))
      (node (ref "U7") (pin "11") (pinfunction "RF_IN_11") (pintype "bidirectional"))
    )
    (net (code "38") (name "Net-(U8-SRT)") (class "Default")
      (node (ref "C9") (pin "1") (pinfunction "1_1") (pintype "bidirectional"))
      (node (ref "U8") (pin "3") (pinfunction "SRT_3") (pintype "bidirectional"))
    )
    (net (code "39") (name "Net-(U8-SWT)") (class "Default")
      (node (ref "C8") (pin "1") (pinfunction "1_1") (pintype "bidirectional"))
      (node (ref "U8") (pin "2") (pinfunction "SWT_2") (pintype "bidirectional"))
    )
    (net (code "40") (name "Net-(U8-~{MR})") (class "Default")
      (node (ref "R27") (pin "1") (pinfunction "1_1") (pintype "passive"))
      (node (ref "R32") (pin "2") (pinfunction "2_2") (pintype "passive"))
      (node (ref "R41") (pin "2") (pinfunction "2_2") (pintype "passive"))
      (node (ref "U8") (pin "1") (pinfunction "~{MR}_1") (pintype "bidirectional"))
    )
    (net (code "41") (name "Net-(U9-IN+)") (class "Default")
      (node (ref "R37") (pin "1") (pinfunction "1_1") (pintype "passive"))
      (node (ref "R38") (pin "2") (pinfunction "2_2") (pintype "passive"))
      (node (ref "U9") (pin "P1") (pinfunction "IN+_P1") (pintype "bidirectional"))
    )
    (net (code "42") (name "Net-(U9-IN-)") (class "Default")
      (node (ref "R33") (pin "2") (pinfunction "2_2") (pintype "passive"))
      (node (ref "R35") (pin "2") (pinfunction "2_2") (pintype "passive"))
      (node (ref "R6") (pin "1") (pinfunction "1_1") (pintype "passive"))
      (node (ref "U9") (pin "P3") (pinfunction "IN-_P3") (pintype "bidirectional"))
    )
    (net (code "43") (name "Net-(U10-IN+)") (class "Default")
      (node (ref "R39") (pin "1") (pinfunction "1_1") (pintype "passive"))
      (node (ref "R40") (pin "2") (pinfunction "2_2") (pintype "passive"))
      (node (ref "U10") (pin "P1") (pinfunction "IN+_P1") (pintype "bidirectional"))
    )
    (net (code "44") (name "Net-(U10-IN-)") (class "Default")
      (node (ref "R34") (pin "2") (pinfunction "2_2") (pintype "passive"))
      (node (ref "R36") (pin "2") (pinfunction "2_2") (pintype "passive"))
      (node (ref "R7") (pin "1") (pinfunction "1_1") (pintype "passive"))
      (node (ref "U10") (pin "P3") (pinfunction "IN-_P3") (pintype "bidirectional"))
    )
    (net (code "45") (name "Net-(U15-BCLK)") (class "Default")
      (node (ref "R3") (pin "1") (pinfunction "1_1") (pintype "passive"))
      (node (ref "U15") (pin "4") (pinfunction "BCLK_4") (pintype "bidirectional"))
    )
    (net (code "46") (name "Net-(U15-DATA)") (class "Default")
      (node (ref "R4") (pin "2") (pinfunction "2_2") (pintype "passive"))
      (node (ref "U15") (pin "6") (pinfunction "DATA_6") (pintype "bidirectional"))
    )
    (net (code "47") (name "Net-(U15-WS)") (class "Default")
      (node (ref "R2") (pin "1") (pinfunction "1_1") (pintype "passive"))
      (node (ref "U15") (pin "1") (pinfunction "WS_1") (pintype "bidirectional"))
    )
    (net (code "48") (name "SD_ENABLE") (class "Default")
      (node (ref "ASSY1") (pin "C2") (pinfunction "C2_C2") (pintype "bidirectional"))
      (node (ref "R21") (pin "2") (pinfunction "2_2") (pintype "passive"))
      (node (ref "TP19") (pin "TESTPOINT") (pinfunction "TESTPOINT_TESTPOINT") (pintype "bidirectional"))
      (node (ref "U12") (pin "3") (pinfunction "EN_3") (pintype "bidirectional"))
    )
    (net (code "49") (name "SD_MISO") (class "Default")
      (node (ref "ASSY1") (pin "A4") (pinfunction "A4_A4") (pintype "bidirectional"))
      (node (ref "J1") (pin "7") (pinfunction "DATA0/MISO_7") (pintype "bidirectional"))
      (node (ref "R12") (pin "1") (pinfunction "1_1") (pintype "passive"))
      (node (ref "TP16") (pin "TESTPOINT") (pinfunction "TESTPOINT_TESTPOINT") (pintype "bidirectional"))
      (node (ref "U1") (pin "6") (pinfunction "SDO_6") (pintype "bidirectional"))
    )
    (net (code "50") (name "SD_MOSI") (class "Default")
      (node (ref "ASSY1") (pin "A5") (pinfunction "A5_A5") (pintype "bidirectional"))
      (node (ref "J1") (pin "3") (pinfunction "CMD/MOSI_3") (pintype "bidirectional"))
      (node (ref "R10") (pin "1") (pinfunction "1_1") (pintype "passive"))
      (node (ref "TP15") (pin "TESTPOINT") (pinfunction "TESTPOINT_TESTPOINT") (pintype "bidirectional"))
      (node (ref "U1") (pin "9") (pinfunction "SDI_9") (pintype "bidirectional"))
    )
    (net (code "51") (name "SD_SCLK") (class "Default")
      (node (ref "ASSY1") (pin "A3") (pinfunction "A3_A3") (pintype "bidirectional"))
      (node (ref "J1") (pin "5") (pinfunction "CLK_5") (pintype "bidirectional"))
      (node (ref "TP17") (pin "TESTPOINT") (pinfunction "TESTPOINT_TESTPOINT") (pintype "bidirectional"))
      (node (ref "U1") (pin "7") (pinfunction "SCL_7") (pintype "bidirectional"))
    )
    (net (code "52") (name "SENSE_VCC") (class "Default")
      (node (ref "C5") (pin "1") (pinfunction "1_1") (pintype "bidirectional"))
      (node (ref "C6") (pin "1") (pinfunction "1_1") (pintype "bidirectional"))
      (node (ref "R37") (pin "2") (pinfunction "2_2") (pintype "passive"))
      (node (ref "R39") (pin "2") (pinfunction "2_2") (pintype "passive"))
      (node (ref "U10") (pin "P5") (pinfunction "VCC_P5") (pintype "bidirectional"))
      (node (ref "U14") (pin "1") (pinfunction "VLOAD_1") (pintype "bidirectional"))
      (node (ref "U14") (pin "2") (pinfunction "VLOAD_2") (pintype "bidirectional"))
      (node (ref "U9") (pin "P5") (pinfunction "VCC_P5") (pintype "bidirectional"))
    )
    (net (code "53") (name "SENSORS_SCL") (class "Default")
      (node (ref "ASSY1") (pin "D1") (pinfunction "D1_D1") (pintype "bidirectional"))
      (node (ref "R13") (pin "1") (pinfunction "1_1") (pintype "passive"))
      (node (ref "TP7") (pin "TESTPOINT") (pinfunction "TESTPOINT_TESTPOINT") (pintype "bidirectional"))
      (node (ref "U6") (pin "1") (pinfunction "SCL/SPC_1") (pintype "bidirectional"))
    )
    (net (code "54") (name "SENSORS_SDA") (class "Default")
      (node (ref "ASSY1") (pin "D0") (pinfunction "D0_D0") (pintype "bidirectional"))
      (node (ref "R9") (pin "1") (pinfunction "1_1") (pintype "passive"))
      (node (ref "TP5") (pin "TESTPOINT") (pinfunction "TESTPOINT_TESTPOINT") (pintype "bidirectional"))
      (node (ref "U6") (pin "4") (pinfunction "MOSI/SDA_4") (pintype "bidirectional"))
    )
    (net (code "55") (name "SERIAL_NUM") (class "Default")
      (node (ref "ASSY1") (pin "B0") (pinfunction "B0_B0") (pintype "bidirectional"))
      (node (ref "R8") (pin "2") (pinfunction "2_2") (pintype "passive"))
      (node (ref "TP13") (pin "TESTPOINT") (pinfunction "TESTPOINT_TESTPOINT") (pintype "bidirectional"))
      (node (ref "U3") (pin "2") (pinfunction "DATA_2") (pintype "input"))
    )
    (net (code "56") (name "VCC") (class "Default")
      (node (ref "ASSY1") (pin "3V3") (pinfunction "3V3_3V3") (pintype "power_in"))
      (node (ref "C10") (pin "1") (pinfunction "1_1") (pintype "bidirectional"))
      (node (ref "C11") (pin "1") (pinfunction "1_1") (pintype "bidirectional"))
      (node (ref "C13") (pin "1") (pinfunction "1_1") (pintype "bidirectional"))
      (node (ref "C4") (pin "1") (pinfunction "1_1") (pintype "bidirectional"))
      (node (ref "R13") (pin "2") (pinfunction "2_2") (pintype "passive"))
      (node (ref "R15") (pin "1") (pinfunction "1_1") (pintype "passive"))
      (node (ref "R16") (pin "1") (pinfunction "1_1") (pintype "passive"))
      (node (ref "R8") (pin "1") (pinfunction "1_1") (pintype "passive"))
      (node (ref "R9") (pin "2") (pinfunction "2_2") (pintype "passive"))
      (node (ref "TP4") (pin "TESTPOINT") (pinfunction "TESTPOINT_TESTPOINT") (pintype "bidirectional"))
      (node (ref "U1") (pin "13") (pinfunction "VCC_13") (pintype "bidirectional"))
      (node (ref "U11") (pin "5") (pinfunction "VSUPP_5") (pintype "bidirectional"))
      (node (ref "U11") (pin "6") (pinfunction "VSUPP_6") (pintype "bidirectional"))
      (node (ref "U12") (pin "5") (pinfunction "VSUPP_5") (pintype "bidirectional"))
      (node (ref "U12") (pin "6") (pinfunction "VSUPP_6") (pintype "bidirectional"))
      (node (ref "U13") (pin "5") (pinfunction "VSUPP_5") (pintype "bidirectional"))
      (node (ref "U13") (pin "6") (pinfunction "VSUPP_6") (pintype "bidirectional"))
      (node (ref "U14") (pin "5") (pinfunction "VSUPP_5") (pintype "bidirectional"))
      (node (ref "U14") (pin "6") (pinfunction "VSUPP_6") (pintype "bidirectional"))
      (node (ref "U15") (pin "2") (pinfunction "SELECT_2") (pintype "bidirectional"))
      (node (ref "U15") (pin "5") (pinfunction "VDD_5") (pintype "bidirectional"))
      (node (ref "U6") (pin "10") (pinfunction "VDD_IO_10") (pintype "bidirectional"))
      (node (ref "U6") (pin "2") (pinfunction "CS_2") (pintype "bidirectional"))
      (node (ref "U6") (pin "9") (pinfunction "VCC_9") (pintype "bidirectional"))
    )
    (net (code "57") (name "VCC_RF") (class "Default")
      (node (ref "C2") (pin "2") (pinfunction "2_2") (pintype "bidirectional"))
      (node (ref "U2") (pin "2") (pinfunction "VCC_2") (pintype "power_in"))
      (node (ref "U2") (pin "6") (pinfunction "PON_6") (pintype "input"))
      (node (ref "U7") (pin "14") (pinfunction "VCC_RF_14") (pintype "bidirectional"))
    )
    (net (code "58") (name "WDI") (class "Default")
      (node (ref "ASSY1") (pin "DAC") (pinfunction "DAC_DAC") (pintype "bidirectional"))
      (node (ref "R14") (pin "1") (pinfunction "1_1") (pintype "passive"))
      (node (ref "TP25") (pin "TESTPOINT") (pinfunction "TESTPOINT_TESTPOINT") (pintype "bidirectional"))
      (node (ref "U1") (pin "2") (pinfunction "WDI_2") (pintype "bidirectional"))
      (node (ref "U8") (pin "6") (pinfunction "WDI_6") (pintype "bidirectional"))
    )
    (net (code "59") (name "WIFI_PWR_EN") (class "Default")
      (node (ref "ASSY1") (pin "B1") (pinfunction "B1_B1") (pintype "bidirectional"))
      (node (ref "R23") (pin "2") (pinfunction "2_2") (pintype "passive"))
      (node (ref "TP1") (pin "TESTPOINT") (pinfunction "TESTPOINT_TESTPOINT") (pintype "bidirectional"))
      (node (ref "U13") (pin "3") (pinfunction "EN_3") (pintype "bidirectional"))
    )
    (net (code "60") (name "WIFI_RXD") (class "Default")
      (node (ref "ASSY1") (pin "C1") (pinfunction "C1_C1") (pintype "bidirectional"))
      (node (ref "ASSY2") (pin "7") (pinfunction "RXI_7") (pintype "bidirectional"))
      (node (ref "TP3") (pin "TESTPOINT") (pinfunction "TESTPOINT_TESTPOINT") (pintype "bidirectional"))
    )
    (net (code "61") (name "WIFI_TXD") (class "Default")
      (node (ref "ASSY1") (pin "C0") (pinfunction "C0_C0") (pintype "bidirectional"))
      (node (ref "ASSY2") (pin "2") (pinfunction "TXO_2") (pintype "bidirectional"))
      (node (ref "TP2") (pin "TESTPOINT") (pinfunction "TESTPOINT_TESTPOINT") (pintype "bidirectional"))
    )
    (net (code "62") (name "unconnected-(ASSY1-PadVBAT)") (class "Default")
      (node (ref "ASSY1") (pin "VBAT") (pinfunction "VBAT_VBAT") (pintype "passive"))
    )
    (net (code "63") (name "unconnected-(ASSY2-IO0-Pad5)") (class "Default")
      (node (ref "ASSY2") (pin "5") (pinfunction "IO0_5") (pintype "bidirectional"))
    )
    (net (code "64") (name "unconnected-(ASSY2-IO2-Pad3)") (class "Default")
      (node (ref "ASSY2") (pin "3") (pinfunction "IO2_3") (pintype "bidirectional"))
    )
    (net (code "65") (name "unconnected-(J1-DATA1{slash}RSV-Pad8)") (class "Default")
      (node (ref "J1") (pin "8") (pinfunction "DATA1/RSV_8") (pintype "bidirectional"))
    )
    (net (code "66") (name "unconnected-(J1-DATA2{slash}NC-Pad1)") (class "Default")
      (node (ref "J1") (pin "1") (pinfunction "DATA2/NC_1") (pintype "bidirectional"))
    )
    (net (code "67") (name "unconnected-(U1-CLKOUT{slash}~{IRQ3}-Pad8)") (class "Default")
      (node (ref "U1") (pin "8") (pinfunction "CLKOUT/~{IRQ3}_8") (pintype "bidirectional"))
    )
    (net (code "68") (name "unconnected-(U1-~{IRQ2}-Pad4)") (class "Default")
      (node (ref "U1") (pin "4") (pinfunction "~{IRQ2}_4") (pintype "bidirectional"))
    )
    (net (code "69") (name "unconnected-(U1-~{RST}-Pad1)") (class "Default")
      (node (ref "U1") (pin "1") (pinfunction "~{RST}_1") (pintype "bidirectional"))
    )
    (net (code "70") (name "unconnected-(U3-NC-Pad6)") (class "Default")
      (node (ref "U3") (pin "6") (pinfunction "NC_6") (pintype "no_connect"))
    )
    (net (code "71") (name "unconnected-(U3-NC_2-Pad3)") (class "Default")
      (node (ref "U3") (pin "3") (pinfunction "NC_2_3") (pintype "no_connect"))
    )
    (net (code "72") (name "unconnected-(U3-NC_3-Pad4)") (class "Default")
      (node (ref "U3") (pin "4") (pinfunction "NC_3_4") (pintype "no_connect"))
    )
    (net (code "73") (name "unconnected-(U3-NC_4-Pad5)") (class "Default")
      (node (ref "U3") (pin "5") (pinfunction "NC_4_5") (pintype "no_connect"))
    )
    (net (code "74") (name "unconnected-(U6-INT2-Pad11)") (class "Default")
      (node (ref "U6") (pin "11") (pinfunction "INT2_11") (pintype "bidirectional"))
    )
    (net (code "75") (name "unconnected-(U7-EXTINT-Pad5)") (class "Default")
      (node (ref "U7") (pin "5") (pinfunction "EXTINT_5") (pintype "bidirectional"))
    )
    (net (code "76") (name "unconnected-(U7-LNA_EN-Pad13)") (class "Default")
      (node (ref "U7") (pin "13") (pinfunction "LNA_EN_13") (pintype "bidirectional"))
    )
    (net (code "77") (name "unconnected-(U7-SCL-Pad17)") (class "Default")
      (node (ref "U7") (pin "17") (pinfunction "SCL_17") (pintype "bidirectional"))
    )
    (net (code "78") (name "unconnected-(U7-SDA-Pad16)") (class "Default")
      (node (ref "U7") (pin "16") (pinfunction "SDA_16") (pintype "bidirectional"))
    )
    (net (code "79") (name "unconnected-(U7-V_ANT-Pad15)") (class "Default")
      (node (ref "U7") (pin "15") (pinfunction "V_ANT_15") (pintype "bidirectional"))
    )
    (net (code "80") (name "unconnected-(U7-~{RESET}-Pad9)") (class "Default")
      (node (ref "U7") (pin "9") (pinfunction "~{RESET}_9") (pintype "bidirectional"))
    )
    (net (code "81") (name "unconnected-(U7-~{SAFEBOOT}-Pad18)") (class "Default")
      (node (ref "U7") (pin "18") (pinfunction "~{SAFEBOOT}_18") (pintype "bidirectional"))
    )
    (net (code "82") (name "~{EXTERNAL_RST}") (class "Default")
      (node (ref "ASSY1") (pin "RST") (pinfunction "RST_RST") (pintype "bidirectional"))
      (node (ref "R17") (pin "2") (pinfunction "2_2") (pintype "passive"))
      (node (ref "TP26") (pin "TESTPOINT") (pinfunction "TESTPOINT_TESTPOINT") (pintype "bidirectional"))
      (node (ref "U8") (pin "7") (pinfunction "~{RESET}_7") (pintype "bidirectional"))
    )
    (net (code "83") (name "~{RTC_CS}") (class "Default")
      (node (ref "ASSY1") (pin "C5") (pinfunction "C5_C5") (pintype "bidirectional"))
      (node (ref "R16") (pin "2") (pinfunction "2_2") (pintype "passive"))
      (node (ref "R18") (pin "2") (pinfunction "2_2") (pintype "passive"))
      (node (ref "TP23") (pin "TESTPOINT") (pinfunction "TESTPOINT_TESTPOINT") (pintype "bidirectional"))
      (node (ref "U1") (pin "12") (pinfunction "~{CS}_12") (pintype "bidirectional"))
    )
    (net (code "84") (name "~{RTC_INT1}") (class "Default")
      (node (ref "ASSY1") (pin "D7") (pinfunction "D7_D7") (pintype "bidirectional"))
      (node (ref "R15") (pin "2") (pinfunction "2_2") (pintype "passive"))
      (node (ref "TP24") (pin "TESTPOINT") (pinfunction "TESTPOINT_TESTPOINT") (pintype "bidirectional"))
      (node (ref "U1") (pin "11") (pinfunction "FOUT/~{IRQ1}_11") (pintype "bidirectional"))
    )
    (net (code "85") (name "~{SD_CS}") (class "Default")
      (node (ref "ASSY1") (pin "A2") (pinfunction "A2_A2") (pintype "bidirectional"))
      (node (ref "J1") (pin "2") (pinfunction "DATA3-CD/CS_N_2") (pintype "bidirectional"))
      (node (ref "R11") (pin "1") (pinfunction "1_1") (pintype "passive"))
      (node (ref "TP18") (pin "TESTPOINT") (pinfunction "TESTPOINT_TESTPOINT") (pintype "bidirectional"))
    )
    (net (code "86") (name "~{SD_DETECT}") (class "Default")
      (node (ref "ASSY1") (pin "D6") (pinfunction "D6_D6") (pintype "bidirectional"))
      (node (ref "J1") (pin "A") (pinfunction "A_A") (pintype "bidirectional"))
      (node (ref "R20") (pin "1") (pinfunction "1_1") (pintype "passive"))
      (node (ref "TP11") (pin "TESTPOINT") (pinfunction "TESTPOINT_TESTPOINT") (pintype "bidirectional"))
    )
  )
)
